# axiom_beta_interface_dummy_v0_13_r1_4.net
KiCad netlist of a schematic drawn in EAGLE
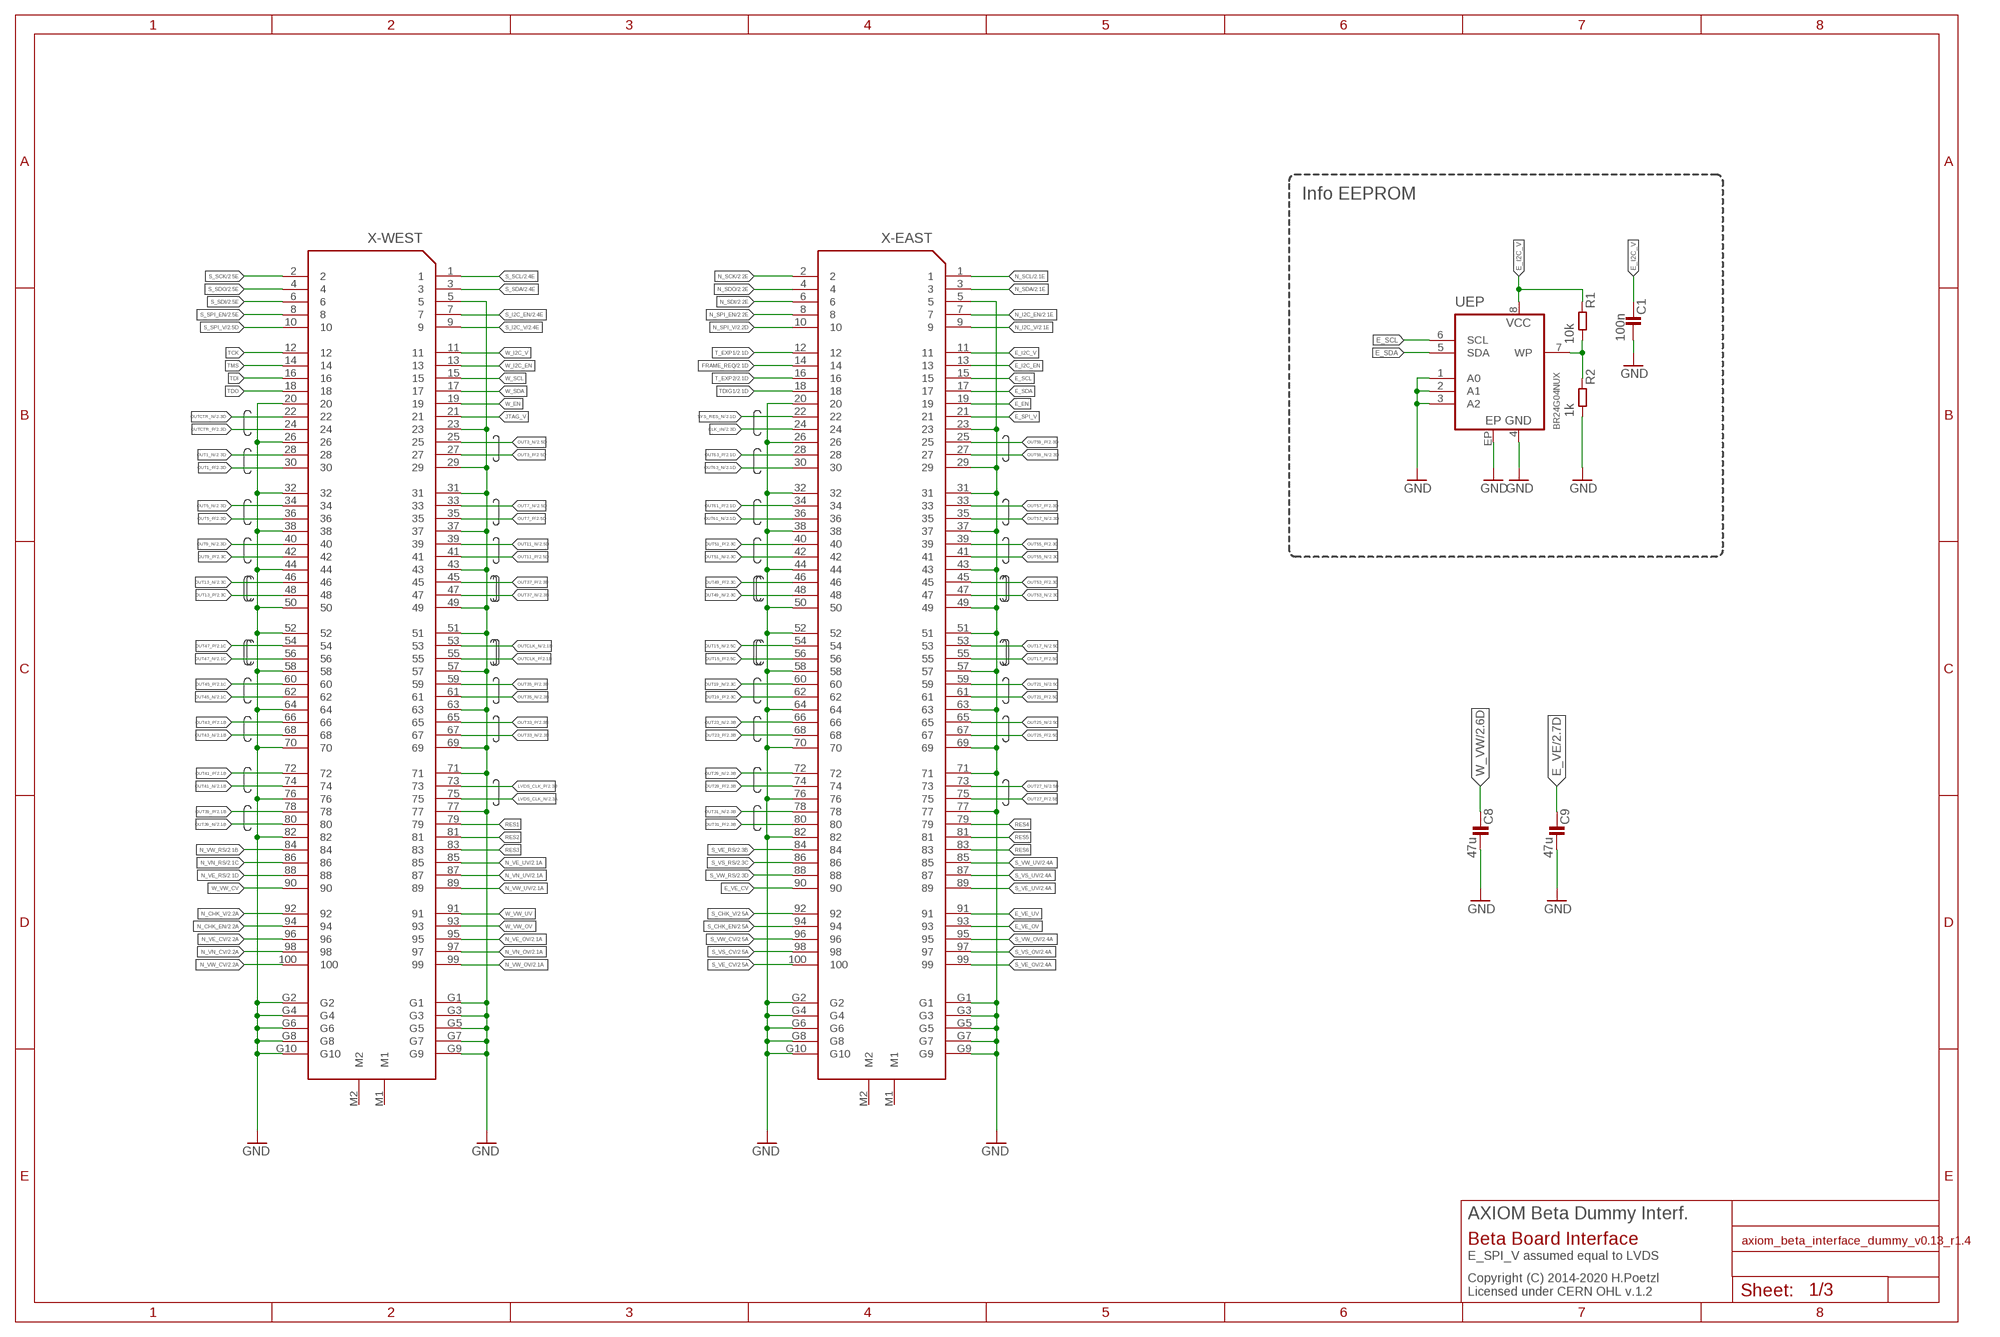
[diagram p0: schematic, sheet 1]
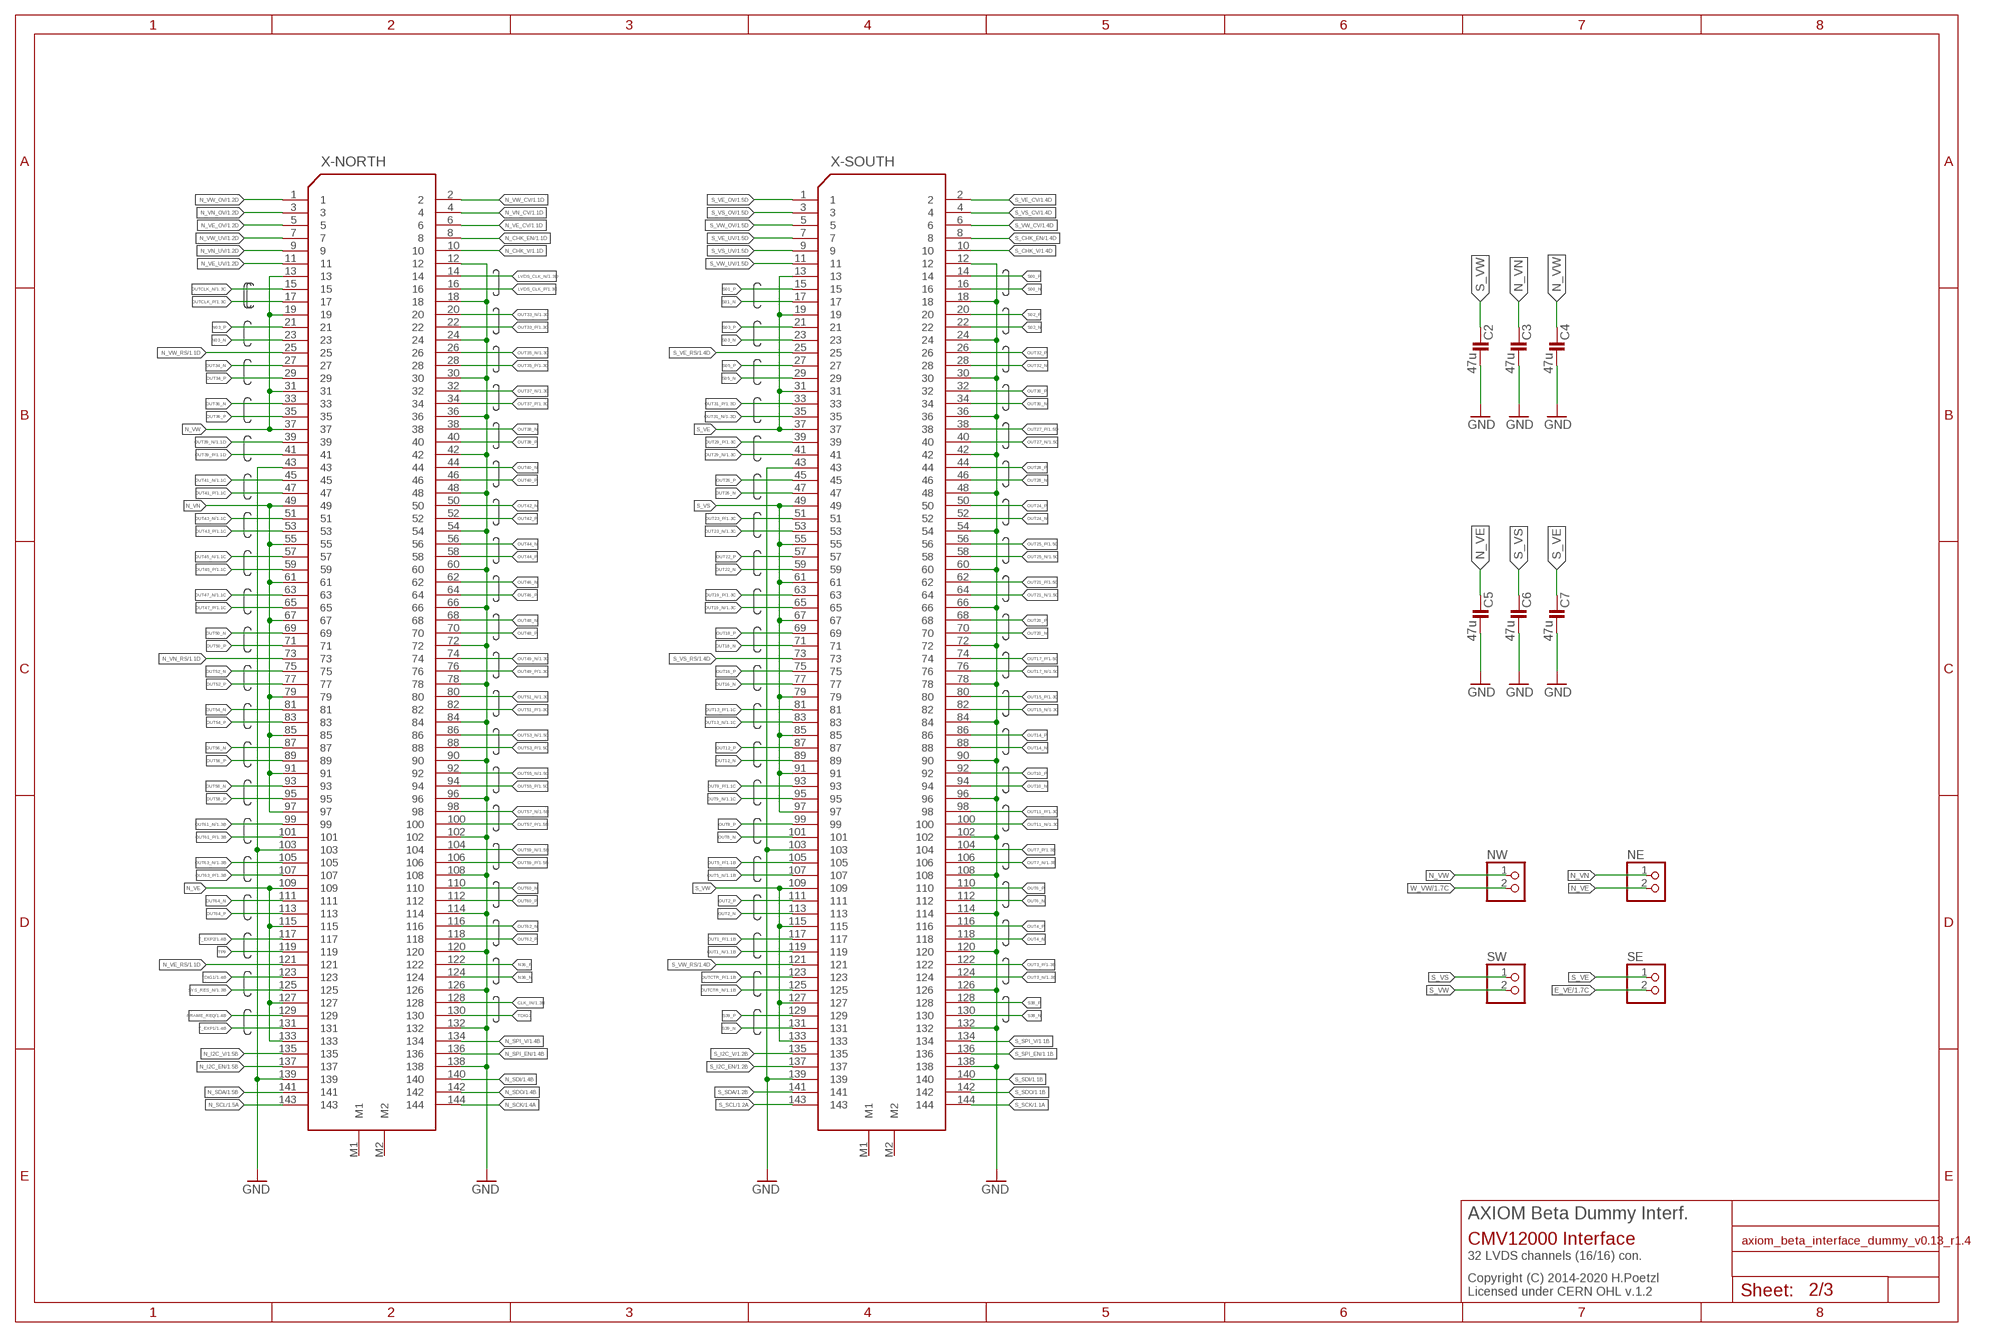
[diagram p1: schematic, sheet 2]
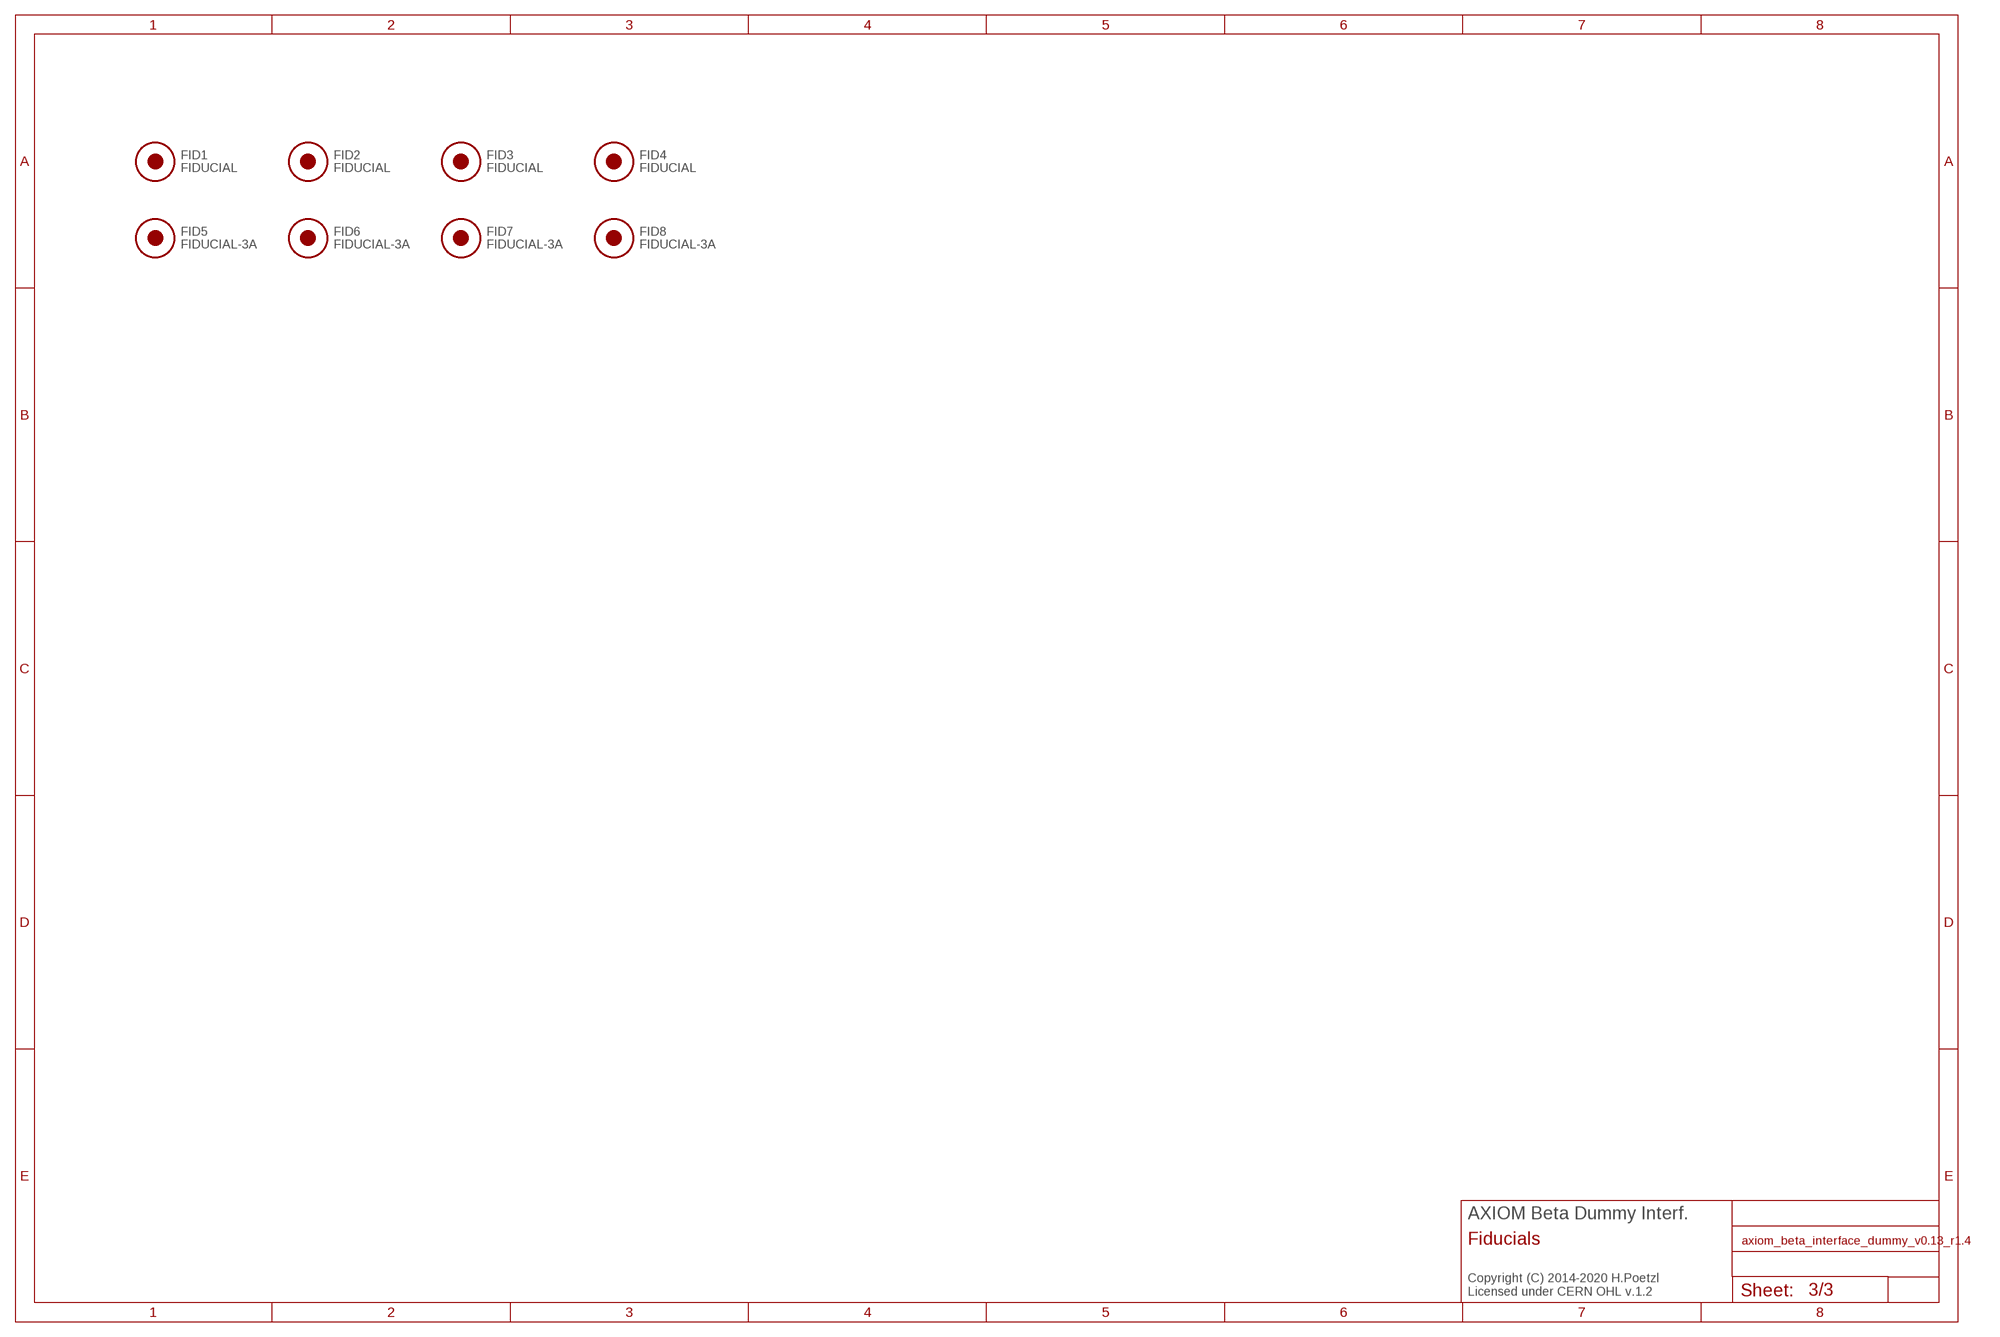
[diagram p2: schematic, sheet 3]

(export (version "E")
  (design (tool "Eeschema 10.0.6"))
  (components
    (comp (ref "C2")
      (value "47u")
      (footprint "eagle-import:0805-B")
      (libsource (lib "eagle-import") (part "C0805-B"))
    )
    (comp (ref "C3")
      (value "47u")
      (footprint "eagle-import:0805-B")
      (libsource (lib "eagle-import") (part "C0805-B"))
    )
    (comp (ref "C4")
      (value "47u")
      (footprint "eagle-import:0805-B")
      (libsource (lib "eagle-import") (part "C0805-B"))
    )
    (comp (ref "C5")
      (value "47u")
      (footprint "eagle-import:0805-B")
      (libsource (lib "eagle-import") (part "C0805-B"))
    )
    (comp (ref "C6")
      (value "47u")
      (footprint "eagle-import:0805-B")
      (libsource (lib "eagle-import") (part "C0805-B"))
    )
    (comp (ref "C7")
      (value "47u")
      (footprint "eagle-import:0805-B")
      (libsource (lib "eagle-import") (part "C0805-B"))
    )
    (comp (ref "NE")
      (value "PINHD-1X02_2.54")
      (footprint "eagle-import:1X02")
      (libsource (lib "eagle-import") (part "PINHD-1X02_2.54"))
    )
    (comp (ref "NW")
      (value "PINHD-1X02_2.54")
      (footprint "eagle-import:1X02")
      (libsource (lib "eagle-import") (part "PINHD-1X02_2.54"))
    )
    (comp (ref "SE")
      (value "PINHD-1X02_2.54")
      (footprint "eagle-import:1X02")
      (libsource (lib "eagle-import") (part "PINHD-1X02_2.54"))
    )
    (comp (ref "SW")
      (value "PINHD-1X02_2.54")
      (footprint "eagle-import:1X02")
      (libsource (lib "eagle-import") (part "PINHD-1X02_2.54"))
    )
    (comp (ref "X-NORTH")
      (value "FX10-144S")
      (footprint "eagle-import:FX10A-144S")
      (libsource (lib "eagle-import") (part "FX10-144S"))
    )
    (comp (ref "X-SOUTH")
      (value "FX10-144S")
      (footprint "eagle-import:FX10A-144S")
      (libsource (lib "eagle-import") (part "FX10-144S"))
    )
    (comp (ref "C1")
      (value "100n")
      (footprint "eagle-import:0402-B")
      (libsource (lib "eagle-import") (part "C0402-B"))
    )
    (comp (ref "C8")
      (value "47u")
      (footprint "eagle-import:0805-B")
      (libsource (lib "eagle-import") (part "C0805-B"))
    )
    (comp (ref "C9")
      (value "47u")
      (footprint "eagle-import:0805-B")
      (libsource (lib "eagle-import") (part "C0805-B"))
    )
    (comp (ref "R1")
      (value "10k")
      (footprint "eagle-import:0402-B")
      (libsource (lib "eagle-import") (part "R0402-B"))
    )
    (comp (ref "R2")
      (value "1k")
      (footprint "eagle-import:0402-B")
      (libsource (lib "eagle-import") (part "R0402-B"))
    )
    (comp (ref "UEP")
      (value "BR24G04NUX")
      (footprint "eagle-import:DFN200X300X100-9N")
      (libsource (lib "eagle-import") (part "BR24G04NUX"))
    )
    (comp (ref "X-EAST")
      (value "FX10-100/10P")
      (footprint "eagle-import:FX10A-100P_10")
      (libsource (lib "eagle-import") (part "FX10-100/10P"))
    )
    (comp (ref "X-WEST")
      (value "FX10-100/10P")
      (footprint "eagle-import:FX10A-100P_10")
      (libsource (lib "eagle-import") (part "FX10-100/10P"))
    )
    (comp (ref "FID1")
      (value "FIDUCIAL")
      (footprint "eagle-import:FID_ARROW")
      (libsource (lib "eagle-import") (part "FIDUCIAL"))
    )
    (comp (ref "FID2")
      (value "FIDUCIAL")
      (footprint "eagle-import:FID_ARROW")
      (libsource (lib "eagle-import") (part "FIDUCIAL"))
    )
    (comp (ref "FID3")
      (value "FIDUCIAL")
      (footprint "eagle-import:FID_ARROW")
      (libsource (lib "eagle-import") (part "FIDUCIAL"))
    )
    (comp (ref "FID4")
      (value "FIDUCIAL")
      (footprint "eagle-import:FID_ARROW")
      (libsource (lib "eagle-import") (part "FIDUCIAL"))
    )
    (comp (ref "FID5")
      (value "FIDUCIAL-3A")
      (footprint "eagle-import:FID_3ARROW")
      (libsource (lib "eagle-import") (part "FIDUCIAL-3A"))
    )
    (comp (ref "FID6")
      (value "FIDUCIAL-3A")
      (footprint "eagle-import:FID_3ARROW")
      (libsource (lib "eagle-import") (part "FIDUCIAL-3A"))
    )
    (comp (ref "FID7")
      (value "FIDUCIAL-3A")
      (footprint "eagle-import:FID_3ARROW")
      (libsource (lib "eagle-import") (part "FIDUCIAL-3A"))
    )
    (comp (ref "FID8")
      (value "FIDUCIAL-3A")
      (footprint "eagle-import:FID_3ARROW")
      (libsource (lib "eagle-import") (part "FIDUCIAL-3A"))
    )
  )
  (nets
    (net (code "1") (name "CLK_IN") (class "Default")
      (node (ref "X-EAST") (pin "24") (pinfunction "24_24") (pintype "bidirectional"))
      (node (ref "X-NORTH") (pin "128") (pinfunction "128_128") (pintype "bidirectional"))
    )
    (net (code "2") (name "E_EN") (class "Default")
      (node (ref "X-EAST") (pin "19") (pinfunction "19_19") (pintype "bidirectional"))
    )
    (net (code "3") (name "E_I2C_EN") (class "Default")
      (node (ref "X-EAST") (pin "13") (pinfunction "13_13") (pintype "bidirectional"))
    )
    (net (code "4") (name "E_I2C_V") (class "Default")
      (node (ref "C1") (pin "1") (pinfunction "1_1") (pintype "passive"))
      (node (ref "R1") (pin "1") (pinfunction "1_1") (pintype "passive"))
      (node (ref "UEP") (pin "8") (pinfunction "VCC_8") (pintype "power_in"))
      (node (ref "X-EAST") (pin "11") (pinfunction "11_11") (pintype "bidirectional"))
    )
    (net (code "5") (name "E_SCL") (class "Default")
      (node (ref "UEP") (pin "6") (pinfunction "SCL_6") (pintype "input"))
      (node (ref "X-EAST") (pin "15") (pinfunction "15_15") (pintype "bidirectional"))
    )
    (net (code "6") (name "E_SDA") (class "Default")
      (node (ref "UEP") (pin "5") (pinfunction "SDA_5") (pintype "bidirectional"))
      (node (ref "X-EAST") (pin "17") (pinfunction "17_17") (pintype "bidirectional"))
    )
    (net (code "7") (name "E_SPI_V") (class "Default")
      (node (ref "X-EAST") (pin "21") (pinfunction "21_21") (pintype "bidirectional"))
    )
    (net (code "8") (name "E_VE") (class "Default")
      (node (ref "C9") (pin "1") (pinfunction "1_1") (pintype "passive"))
      (node (ref "SE") (pin "2") (pinfunction "2_2") (pintype "passive"))
    )
    (net (code "9") (name "E_VE_CV") (class "Default")
      (node (ref "X-EAST") (pin "90") (pinfunction "90_90") (pintype "bidirectional"))
    )
    (net (code "10") (name "E_VE_OV") (class "Default")
      (node (ref "X-EAST") (pin "93") (pinfunction "93_93") (pintype "bidirectional"))
    )
    (net (code "11") (name "E_VE_UV") (class "Default")
      (node (ref "X-EAST") (pin "91") (pinfunction "91_91") (pintype "bidirectional"))
    )
    (net (code "12") (name "FRAME_REQ") (class "Default")
      (node (ref "X-EAST") (pin "14") (pinfunction "14_14") (pintype "bidirectional"))
      (node (ref "X-NORTH") (pin "129") (pinfunction "129_129") (pintype "bidirectional"))
    )
    (net (code "13") (name "GND") (class "Default")
      (node (ref "C1") (pin "2") (pinfunction "2_2") (pintype "passive"))
      (node (ref "C2") (pin "2") (pinfunction "2_2") (pintype "passive"))
      (node (ref "C3") (pin "2") (pinfunction "2_2") (pintype "passive"))
      (node (ref "C4") (pin "2") (pinfunction "2_2") (pintype "passive"))
      (node (ref "C5") (pin "2") (pinfunction "2_2") (pintype "passive"))
      (node (ref "C6") (pin "2") (pinfunction "2_2") (pintype "passive"))
      (node (ref "C7") (pin "2") (pinfunction "2_2") (pintype "passive"))
      (node (ref "C8") (pin "2") (pinfunction "2_2") (pintype "passive"))
      (node (ref "C9") (pin "2") (pinfunction "2_2") (pintype "passive"))
      (node (ref "R2") (pin "2") (pinfunction "2_2") (pintype "passive"))
      (node (ref "UEP") (pin "1") (pinfunction "A0_1") (pintype "input"))
      (node (ref "UEP") (pin "2") (pinfunction "A1_2") (pintype "input"))
      (node (ref "UEP") (pin "3") (pinfunction "A2_3") (pintype "input"))
      (node (ref "UEP") (pin "4") (pinfunction "GND_4") (pintype "passive"))
      (node (ref "UEP") (pin "EP") (pinfunction "EP_EP") (pintype "passive"))
      (node (ref "X-EAST") (pin "20") (pinfunction "20_20") (pintype "bidirectional"))
      (node (ref "X-EAST") (pin "23") (pinfunction "23_23") (pintype "bidirectional"))
      (node (ref "X-EAST") (pin "26") (pinfunction "26_26") (pintype "bidirectional"))
      (node (ref "X-EAST") (pin "29") (pinfunction "29_29") (pintype "bidirectional"))
      (node (ref "X-EAST") (pin "31") (pinfunction "31_31") (pintype "bidirectional"))
      (node (ref "X-EAST") (pin "32") (pinfunction "32_32") (pintype "bidirectional"))
      (node (ref "X-EAST") (pin "37") (pinfunction "37_37") (pintype "bidirectional"))
      (node (ref "X-EAST") (pin "38") (pinfunction "38_38") (pintype "bidirectional"))
      (node (ref "X-EAST") (pin "43") (pinfunction "43_43") (pintype "bidirectional"))
      (node (ref "X-EAST") (pin "44") (pinfunction "44_44") (pintype "bidirectional"))
      (node (ref "X-EAST") (pin "49") (pinfunction "49_49") (pintype "bidirectional"))
      (node (ref "X-EAST") (pin "5") (pinfunction "5_5") (pintype "bidirectional"))
      (node (ref "X-EAST") (pin "50") (pinfunction "50_50") (pintype "bidirectional"))
      (node (ref "X-EAST") (pin "51") (pinfunction "51_51") (pintype "bidirectional"))
      (node (ref "X-EAST") (pin "52") (pinfunction "52_52") (pintype "bidirectional"))
      (node (ref "X-EAST") (pin "57") (pinfunction "57_57") (pintype "bidirectional"))
      (node (ref "X-EAST") (pin "58") (pinfunction "58_58") (pintype "bidirectional"))
      (node (ref "X-EAST") (pin "63") (pinfunction "63_63") (pintype "bidirectional"))
      (node (ref "X-EAST") (pin "64") (pinfunction "64_64") (pintype "bidirectional"))
      (node (ref "X-EAST") (pin "69") (pinfunction "69_69") (pintype "bidirectional"))
      (node (ref "X-EAST") (pin "70") (pinfunction "70_70") (pintype "bidirectional"))
      (node (ref "X-EAST") (pin "71") (pinfunction "71_71") (pintype "bidirectional"))
      (node (ref "X-EAST") (pin "76") (pinfunction "76_76") (pintype "bidirectional"))
      (node (ref "X-EAST") (pin "77") (pinfunction "77_77") (pintype "bidirectional"))
      (node (ref "X-EAST") (pin "82") (pinfunction "82_82") (pintype "bidirectional"))
      (node (ref "X-EAST") (pin "G1") (pinfunction "G1_G1") (pintype "bidirectional"))
      (node (ref "X-EAST") (pin "G10") (pinfunction "G10_G10") (pintype "bidirectional"))
      (node (ref "X-EAST") (pin "G2") (pinfunction "G2_G2") (pintype "bidirectional"))
      (node (ref "X-EAST") (pin "G3") (pinfunction "G3_G3") (pintype "bidirectional"))
      (node (ref "X-EAST") (pin "G4") (pinfunction "G4_G4") (pintype "bidirectional"))
      (node (ref "X-EAST") (pin "G5") (pinfunction "G5_G5") (pintype "bidirectional"))
      (node (ref "X-EAST") (pin "G6") (pinfunction "G6_G6") (pintype "bidirectional"))
      (node (ref "X-EAST") (pin "G7") (pinfunction "G7_G7") (pintype "bidirectional"))
      (node (ref "X-EAST") (pin "G8") (pinfunction "G8_G8") (pintype "bidirectional"))
      (node (ref "X-EAST") (pin "G9") (pinfunction "G9_G9") (pintype "bidirectional"))
      (node (ref "X-NORTH") (pin "102") (pinfunction "102_102") (pintype "bidirectional"))
      (node (ref "X-NORTH") (pin "103") (pinfunction "103_103") (pintype "bidirectional"))
      (node (ref "X-NORTH") (pin "108") (pinfunction "108_108") (pintype "bidirectional"))
      (node (ref "X-NORTH") (pin "114") (pinfunction "114_114") (pintype "bidirectional"))
      (node (ref "X-NORTH") (pin "12") (pinfunction "12_12") (pintype "bidirectional"))
      (node (ref "X-NORTH") (pin "120") (pinfunction "120_120") (pintype "bidirectional"))
      (node (ref "X-NORTH") (pin "126") (pinfunction "126_126") (pintype "bidirectional"))
      (node (ref "X-NORTH") (pin "132") (pinfunction "132_132") (pintype "bidirectional"))
      (node (ref "X-NORTH") (pin "138") (pinfunction "138_138") (pintype "bidirectional"))
      (node (ref "X-NORTH") (pin "139") (pinfunction "139_139") (pintype "bidirectional"))
      (node (ref "X-NORTH") (pin "18") (pinfunction "18_18") (pintype "bidirectional"))
      (node (ref "X-NORTH") (pin "24") (pinfunction "24_24") (pintype "bidirectional"))
      (node (ref "X-NORTH") (pin "30") (pinfunction "30_30") (pintype "bidirectional"))
      (node (ref "X-NORTH") (pin "36") (pinfunction "36_36") (pintype "bidirectional"))
      (node (ref "X-NORTH") (pin "42") (pinfunction "42_42") (pintype "bidirectional"))
      (node (ref "X-NORTH") (pin "43") (pinfunction "43_43") (pintype "bidirectional"))
      (node (ref "X-NORTH") (pin "48") (pinfunction "48_48") (pintype "bidirectional"))
      (node (ref "X-NORTH") (pin "54") (pinfunction "54_54") (pintype "bidirectional"))
      (node (ref "X-NORTH") (pin "60") (pinfunction "60_60") (pintype "bidirectional"))
      (node (ref "X-NORTH") (pin "66") (pinfunction "66_66") (pintype "bidirectional"))
      (node (ref "X-NORTH") (pin "72") (pinfunction "72_72") (pintype "bidirectional"))
      (node (ref "X-NORTH") (pin "78") (pinfunction "78_78") (pintype "bidirectional"))
      (node (ref "X-NORTH") (pin "84") (pinfunction "84_84") (pintype "bidirectional"))
      (node (ref "X-NORTH") (pin "90") (pinfunction "90_90") (pintype "bidirectional"))
      (node (ref "X-NORTH") (pin "96") (pinfunction "96_96") (pintype "bidirectional"))
      (node (ref "X-SOUTH") (pin "102") (pinfunction "102_102") (pintype "bidirectional"))
      (node (ref "X-SOUTH") (pin "103") (pinfunction "103_103") (pintype "bidirectional"))
      (node (ref "X-SOUTH") (pin "108") (pinfunction "108_108") (pintype "bidirectional"))
      (node (ref "X-SOUTH") (pin "114") (pinfunction "114_114") (pintype "bidirectional"))
      (node (ref "X-SOUTH") (pin "12") (pinfunction "12_12") (pintype "bidirectional"))
      (node (ref "X-SOUTH") (pin "120") (pinfunction "120_120") (pintype "bidirectional"))
      (node (ref "X-SOUTH") (pin "126") (pinfunction "126_126") (pintype "bidirectional"))
      (node (ref "X-SOUTH") (pin "132") (pinfunction "132_132") (pintype "bidirectional"))
      (node (ref "X-SOUTH") (pin "138") (pinfunction "138_138") (pintype "bidirectional"))
      (node (ref "X-SOUTH") (pin "139") (pinfunction "139_139") (pintype "bidirectional"))
      (node (ref "X-SOUTH") (pin "18") (pinfunction "18_18") (pintype "bidirectional"))
      (node (ref "X-SOUTH") (pin "24") (pinfunction "24_24") (pintype "bidirectional"))
      (node (ref "X-SOUTH") (pin "30") (pinfunction "30_30") (pintype "bidirectional"))
      (node (ref "X-SOUTH") (pin "36") (pinfunction "36_36") (pintype "bidirectional"))
      (node (ref "X-SOUTH") (pin "42") (pinfunction "42_42") (pintype "bidirectional"))
      (node (ref "X-SOUTH") (pin "43") (pinfunction "43_43") (pintype "bidirectional"))
      (node (ref "X-SOUTH") (pin "48") (pinfunction "48_48") (pintype "bidirectional"))
      (node (ref "X-SOUTH") (pin "54") (pinfunction "54_54") (pintype "bidirectional"))
      (node (ref "X-SOUTH") (pin "60") (pinfunction "60_60") (pintype "bidirectional"))
      (node (ref "X-SOUTH") (pin "66") (pinfunction "66_66") (pintype "bidirectional"))
      (node (ref "X-SOUTH") (pin "72") (pinfunction "72_72") (pintype "bidirectional"))
      (node (ref "X-SOUTH") (pin "78") (pinfunction "78_78") (pintype "bidirectional"))
      (node (ref "X-SOUTH") (pin "84") (pinfunction "84_84") (pintype "bidirectional"))
      (node (ref "X-SOUTH") (pin "90") (pinfunction "90_90") (pintype "bidirectional"))
      (node (ref "X-SOUTH") (pin "96") (pinfunction "96_96") (pintype "bidirectional"))
      (node (ref "X-WEST") (pin "20") (pinfunction "20_20") (pintype "bidirectional"))
      (node (ref "X-WEST") (pin "23") (pinfunction "23_23") (pintype "bidirectional"))
      (node (ref "X-WEST") (pin "26") (pinfunction "26_26") (pintype "bidirectional"))
      (node (ref "X-WEST") (pin "29") (pinfunction "29_29") (pintype "bidirectional"))
      (node (ref "X-WEST") (pin "31") (pinfunction "31_31") (pintype "bidirectional"))
      (node (ref "X-WEST") (pin "32") (pinfunction "32_32") (pintype "bidirectional"))
      (node (ref "X-WEST") (pin "37") (pinfunction "37_37") (pintype "bidirectional"))
      (node (ref "X-WEST") (pin "38") (pinfunction "38_38") (pintype "bidirectional"))
      (node (ref "X-WEST") (pin "43") (pinfunction "43_43") (pintype "bidirectional"))
      (node (ref "X-WEST") (pin "44") (pinfunction "44_44") (pintype "bidirectional"))
      (node (ref "X-WEST") (pin "49") (pinfunction "49_49") (pintype "bidirectional"))
      (node (ref "X-WEST") (pin "5") (pinfunction "5_5") (pintype "bidirectional"))
      (node (ref "X-WEST") (pin "50") (pinfunction "50_50") (pintype "bidirectional"))
      (node (ref "X-WEST") (pin "51") (pinfunction "51_51") (pintype "bidirectional"))
      (node (ref "X-WEST") (pin "52") (pinfunction "52_52") (pintype "bidirectional"))
      (node (ref "X-WEST") (pin "57") (pinfunction "57_57") (pintype "bidirectional"))
      (node (ref "X-WEST") (pin "58") (pinfunction "58_58") (pintype "bidirectional"))
      (node (ref "X-WEST") (pin "63") (pinfunction "63_63") (pintype "bidirectional"))
      (node (ref "X-WEST") (pin "64") (pinfunction "64_64") (pintype "bidirectional"))
      (node (ref "X-WEST") (pin "69") (pinfunction "69_69") (pintype "bidirectional"))
      (node (ref "X-WEST") (pin "70") (pinfunction "70_70") (pintype "bidirectional"))
      (node (ref "X-WEST") (pin "71") (pinfunction "71_71") (pintype "bidirectional"))
      (node (ref "X-WEST") (pin "76") (pinfunction "76_76") (pintype "bidirectional"))
      (node (ref "X-WEST") (pin "77") (pinfunction "77_77") (pintype "bidirectional"))
      (node (ref "X-WEST") (pin "82") (pinfunction "82_82") (pintype "bidirectional"))
      (node (ref "X-WEST") (pin "G1") (pinfunction "G1_G1") (pintype "bidirectional"))
      (node (ref "X-WEST") (pin "G10") (pinfunction "G10_G10") (pintype "bidirectional"))
      (node (ref "X-WEST") (pin "G2") (pinfunction "G2_G2") (pintype "bidirectional"))
      (node (ref "X-WEST") (pin "G3") (pinfunction "G3_G3") (pintype "bidirectional"))
      (node (ref "X-WEST") (pin "G4") (pinfunction "G4_G4") (pintype "bidirectional"))
      (node (ref "X-WEST") (pin "G5") (pinfunction "G5_G5") (pintype "bidirectional"))
      (node (ref "X-WEST") (pin "G6") (pinfunction "G6_G6") (pintype "bidirectional"))
      (node (ref "X-WEST") (pin "G7") (pinfunction "G7_G7") (pintype "bidirectional"))
      (node (ref "X-WEST") (pin "G8") (pinfunction "G8_G8") (pintype "bidirectional"))
      (node (ref "X-WEST") (pin "G9") (pinfunction "G9_G9") (pintype "bidirectional"))
    )
    (net (code "14") (name "JTAG_V") (class "Default")
      (node (ref "X-WEST") (pin "21") (pinfunction "21_21") (pintype "bidirectional"))
    )
    (net (code "15") (name "LVDS_CLK_N") (class "Default")
      (node (ref "X-NORTH") (pin "14") (pinfunction "14_14") (pintype "bidirectional"))
      (node (ref "X-WEST") (pin "75") (pinfunction "75_75") (pintype "bidirectional"))
    )
    (net (code "16") (name "LVDS_CLK_P") (class "Default")
      (node (ref "X-NORTH") (pin "16") (pinfunction "16_16") (pintype "bidirectional"))
      (node (ref "X-WEST") (pin "73") (pinfunction "73_73") (pintype "bidirectional"))
    )
    (net (code "17") (name "N03_N") (class "Default")
      (node (ref "X-NORTH") (pin "23") (pinfunction "23_23") (pintype "bidirectional"))
    )
    (net (code "18") (name "N03_P") (class "Default")
      (node (ref "X-NORTH") (pin "21") (pinfunction "21_21") (pintype "bidirectional"))
    )
    (net (code "19") (name "N36_N") (class "Default")
      (node (ref "X-NORTH") (pin "124") (pinfunction "124_124") (pintype "bidirectional"))
    )
    (net (code "20") (name "N36_P") (class "Default")
      (node (ref "X-NORTH") (pin "122") (pinfunction "122_122") (pintype "bidirectional"))
    )
    (net (code "21") (name "N_CHK_EN") (class "Default")
      (node (ref "X-NORTH") (pin "8") (pinfunction "8_8") (pintype "bidirectional"))
      (node (ref "X-WEST") (pin "94") (pinfunction "94_94") (pintype "bidirectional"))
    )
    (net (code "22") (name "N_CHK_V") (class "Default")
      (node (ref "X-NORTH") (pin "10") (pinfunction "10_10") (pintype "bidirectional"))
      (node (ref "X-WEST") (pin "92") (pinfunction "92_92") (pintype "bidirectional"))
    )
    (net (code "23") (name "N_I2C_EN") (class "Default")
      (node (ref "X-EAST") (pin "7") (pinfunction "7_7") (pintype "bidirectional"))
      (node (ref "X-NORTH") (pin "137") (pinfunction "137_137") (pintype "bidirectional"))
    )
    (net (code "24") (name "N_I2C_V") (class "Default")
      (node (ref "X-EAST") (pin "9") (pinfunction "9_9") (pintype "bidirectional"))
      (node (ref "X-NORTH") (pin "135") (pinfunction "135_135") (pintype "bidirectional"))
    )
    (net (code "25") (name "N_SCK") (class "Default")
      (node (ref "X-EAST") (pin "2") (pinfunction "2_2") (pintype "bidirectional"))
      (node (ref "X-NORTH") (pin "144") (pinfunction "144_144") (pintype "bidirectional"))
    )
    (net (code "26") (name "N_SCL") (class "Default")
      (node (ref "X-EAST") (pin "1") (pinfunction "1_1") (pintype "bidirectional"))
      (node (ref "X-NORTH") (pin "143") (pinfunction "143_143") (pintype "bidirectional"))
    )
    (net (code "27") (name "N_SDA") (class "Default")
      (node (ref "X-EAST") (pin "3") (pinfunction "3_3") (pintype "bidirectional"))
      (node (ref "X-NORTH") (pin "141") (pinfunction "141_141") (pintype "bidirectional"))
    )
    (net (code "28") (name "N_SDI") (class "Default")
      (node (ref "X-EAST") (pin "6") (pinfunction "6_6") (pintype "bidirectional"))
      (node (ref "X-NORTH") (pin "140") (pinfunction "140_140") (pintype "bidirectional"))
    )
    (net (code "29") (name "N_SDO") (class "Default")
      (node (ref "X-EAST") (pin "4") (pinfunction "4_4") (pintype "bidirectional"))
      (node (ref "X-NORTH") (pin "142") (pinfunction "142_142") (pintype "bidirectional"))
    )
    (net (code "30") (name "N_SPI_EN") (class "Default")
      (node (ref "X-EAST") (pin "8") (pinfunction "8_8") (pintype "bidirectional"))
      (node (ref "X-NORTH") (pin "136") (pinfunction "136_136") (pintype "bidirectional"))
    )
    (net (code "31") (name "N_SPI_V") (class "Default")
      (node (ref "X-EAST") (pin "10") (pinfunction "10_10") (pintype "bidirectional"))
      (node (ref "X-NORTH") (pin "134") (pinfunction "134_134") (pintype "bidirectional"))
    )
    (net (code "32") (name "N_VE") (class "Default")
      (node (ref "C5") (pin "1") (pinfunction "1_1") (pintype "passive"))
      (node (ref "NE") (pin "2") (pinfunction "2_2") (pintype "passive"))
      (node (ref "X-NORTH") (pin "109") (pinfunction "109_109") (pintype "bidirectional"))
      (node (ref "X-NORTH") (pin "115") (pinfunction "115_115") (pintype "bidirectional"))
      (node (ref "X-NORTH") (pin "127") (pinfunction "127_127") (pintype "bidirectional"))
      (node (ref "X-NORTH") (pin "133") (pinfunction "133_133") (pintype "bidirectional"))
    )
    (net (code "33") (name "N_VE_CV") (class "Default")
      (node (ref "X-NORTH") (pin "6") (pinfunction "6_6") (pintype "bidirectional"))
      (node (ref "X-WEST") (pin "96") (pinfunction "96_96") (pintype "bidirectional"))
    )
    (net (code "34") (name "N_VE_OV") (class "Default")
      (node (ref "X-NORTH") (pin "5") (pinfunction "5_5") (pintype "bidirectional"))
      (node (ref "X-WEST") (pin "95") (pinfunction "95_95") (pintype "bidirectional"))
    )
    (net (code "35") (name "N_VE_RS") (class "Default")
      (node (ref "X-NORTH") (pin "121") (pinfunction "121_121") (pintype "bidirectional"))
      (node (ref "X-WEST") (pin "88") (pinfunction "88_88") (pintype "bidirectional"))
    )
    (net (code "36") (name "N_VE_UV") (class "Default")
      (node (ref "X-NORTH") (pin "11") (pinfunction "11_11") (pintype "bidirectional"))
      (node (ref "X-WEST") (pin "85") (pinfunction "85_85") (pintype "bidirectional"))
    )
    (net (code "37") (name "N_VN") (class "Default")
      (node (ref "C3") (pin "1") (pinfunction "1_1") (pintype "passive"))
      (node (ref "NE") (pin "1") (pinfunction "1_1") (pintype "passive"))
      (node (ref "X-NORTH") (pin "49") (pinfunction "49_49") (pintype "bidirectional"))
      (node (ref "X-NORTH") (pin "55") (pinfunction "55_55") (pintype "bidirectional"))
      (node (ref "X-NORTH") (pin "61") (pinfunction "61_61") (pintype "bidirectional"))
      (node (ref "X-NORTH") (pin "67") (pinfunction "67_67") (pintype "bidirectional"))
      (node (ref "X-NORTH") (pin "79") (pinfunction "79_79") (pintype "bidirectional"))
      (node (ref "X-NORTH") (pin "85") (pinfunction "85_85") (pintype "bidirectional"))
      (node (ref "X-NORTH") (pin "91") (pinfunction "91_91") (pintype "bidirectional"))
      (node (ref "X-NORTH") (pin "97") (pinfunction "97_97") (pintype "bidirectional"))
    )
    (net (code "38") (name "N_VN_CV") (class "Default")
      (node (ref "X-NORTH") (pin "4") (pinfunction "4_4") (pintype "bidirectional"))
      (node (ref "X-WEST") (pin "98") (pinfunction "98_98") (pintype "bidirectional"))
    )
    (net (code "39") (name "N_VN_OV") (class "Default")
      (node (ref "X-NORTH") (pin "3") (pinfunction "3_3") (pintype "bidirectional"))
      (node (ref "X-WEST") (pin "97") (pinfunction "97_97") (pintype "bidirectional"))
    )
    (net (code "40") (name "N_VN_RS") (class "Default")
      (node (ref "X-NORTH") (pin "73") (pinfunction "73_73") (pintype "bidirectional"))
      (node (ref "X-WEST") (pin "86") (pinfunction "86_86") (pintype "bidirectional"))
    )
    (net (code "41") (name "N_VN_UV") (class "Default")
      (node (ref "X-NORTH") (pin "9") (pinfunction "9_9") (pintype "bidirectional"))
      (node (ref "X-WEST") (pin "87") (pinfunction "87_87") (pintype "bidirectional"))
    )
    (net (code "42") (name "N_VW") (class "Default")
      (node (ref "C4") (pin "1") (pinfunction "1_1") (pintype "passive"))
      (node (ref "NW") (pin "1") (pinfunction "1_1") (pintype "passive"))
      (node (ref "X-NORTH") (pin "13") (pinfunction "13_13") (pintype "bidirectional"))
      (node (ref "X-NORTH") (pin "19") (pinfunction "19_19") (pintype "bidirectional"))
      (node (ref "X-NORTH") (pin "31") (pinfunction "31_31") (pintype "bidirectional"))
      (node (ref "X-NORTH") (pin "37") (pinfunction "37_37") (pintype "bidirectional"))
    )
    (net (code "43") (name "N_VW_CV") (class "Default")
      (node (ref "X-NORTH") (pin "2") (pinfunction "2_2") (pintype "bidirectional"))
      (node (ref "X-WEST") (pin "100") (pinfunction "100_100") (pintype "bidirectional"))
    )
    (net (code "44") (name "N_VW_OV") (class "Default")
      (node (ref "X-NORTH") (pin "1") (pinfunction "1_1") (pintype "bidirectional"))
      (node (ref "X-WEST") (pin "99") (pinfunction "99_99") (pintype "bidirectional"))
    )
    (net (code "45") (name "N_VW_RS") (class "Default")
      (node (ref "X-NORTH") (pin "25") (pinfunction "25_25") (pintype "bidirectional"))
      (node (ref "X-WEST") (pin "84") (pinfunction "84_84") (pintype "bidirectional"))
    )
    (net (code "46") (name "N_VW_UV") (class "Default")
      (node (ref "X-NORTH") (pin "7") (pinfunction "7_7") (pintype "bidirectional"))
      (node (ref "X-WEST") (pin "89") (pinfunction "89_89") (pintype "bidirectional"))
    )
    (net (code "47") (name "Net-(UEP-WP)") (class "Default")
      (node (ref "R1") (pin "2") (pinfunction "2_2") (pintype "passive"))
      (node (ref "R2") (pin "1") (pinfunction "1_1") (pintype "passive"))
      (node (ref "UEP") (pin "7") (pinfunction "WP_7") (pintype "input"))
    )
    (net (code "48") (name "OUT1_N") (class "Default")
      (node (ref "X-SOUTH") (pin "119") (pinfunction "119_119") (pintype "bidirectional"))
      (node (ref "X-WEST") (pin "28") (pinfunction "28_28") (pintype "bidirectional"))
    )
    (net (code "49") (name "OUT1_P") (class "Default")
      (node (ref "X-SOUTH") (pin "117") (pinfunction "117_117") (pintype "bidirectional"))
      (node (ref "X-WEST") (pin "30") (pinfunction "30_30") (pintype "bidirectional"))
    )
    (net (code "50") (name "OUT2_N") (class "Default")
      (node (ref "X-SOUTH") (pin "113") (pinfunction "113_113") (pintype "bidirectional"))
    )
    (net (code "51") (name "OUT2_P") (class "Default")
      (node (ref "X-SOUTH") (pin "111") (pinfunction "111_111") (pintype "bidirectional"))
    )
    (net (code "52") (name "OUT3_N") (class "Default")
      (node (ref "X-SOUTH") (pin "124") (pinfunction "124_124") (pintype "bidirectional"))
      (node (ref "X-WEST") (pin "25") (pinfunction "25_25") (pintype "bidirectional"))
    )
    (net (code "53") (name "OUT3_P") (class "Default")
      (node (ref "X-SOUTH") (pin "122") (pinfunction "122_122") (pintype "bidirectional"))
      (node (ref "X-WEST") (pin "27") (pinfunction "27_27") (pintype "bidirectional"))
    )
    (net (code "54") (name "OUT4_N") (class "Default")
      (node (ref "X-SOUTH") (pin "118") (pinfunction "118_118") (pintype "bidirectional"))
    )
    (net (code "55") (name "OUT4_P") (class "Default")
      (node (ref "X-SOUTH") (pin "116") (pinfunction "116_116") (pintype "bidirectional"))
    )
    (net (code "56") (name "OUT5_N") (class "Default")
      (node (ref "X-SOUTH") (pin "107") (pinfunction "107_107") (pintype "bidirectional"))
      (node (ref "X-WEST") (pin "34") (pinfunction "34_34") (pintype "bidirectional"))
    )
    (net (code "57") (name "OUT5_P") (class "Default")
      (node (ref "X-SOUTH") (pin "105") (pinfunction "105_105") (pintype "bidirectional"))
      (node (ref "X-WEST") (pin "36") (pinfunction "36_36") (pintype "bidirectional"))
    )
    (net (code "58") (name "OUT6_N") (class "Default")
      (node (ref "X-SOUTH") (pin "112") (pinfunction "112_112") (pintype "bidirectional"))
    )
    (net (code "59") (name "OUT6_P") (class "Default")
      (node (ref "X-SOUTH") (pin "110") (pinfunction "110_110") (pintype "bidirectional"))
    )
    (net (code "60") (name "OUT7_N") (class "Default")
      (node (ref "X-SOUTH") (pin "106") (pinfunction "106_106") (pintype "bidirectional"))
      (node (ref "X-WEST") (pin "33") (pinfunction "33_33") (pintype "bidirectional"))
    )
    (net (code "61") (name "OUT7_P") (class "Default")
      (node (ref "X-SOUTH") (pin "104") (pinfunction "104_104") (pintype "bidirectional"))
      (node (ref "X-WEST") (pin "35") (pinfunction "35_35") (pintype "bidirectional"))
    )
    (net (code "62") (name "OUT8_N") (class "Default")
      (node (ref "X-SOUTH") (pin "101") (pinfunction "101_101") (pintype "bidirectional"))
    )
    (net (code "63") (name "OUT8_P") (class "Default")
      (node (ref "X-SOUTH") (pin "99") (pinfunction "99_99") (pintype "bidirectional"))
    )
    (net (code "64") (name "OUT9_N") (class "Default")
      (node (ref "X-SOUTH") (pin "95") (pinfunction "95_95") (pintype "bidirectional"))
      (node (ref "X-WEST") (pin "40") (pinfunction "40_40") (pintype "bidirectional"))
    )
    (net (code "65") (name "OUT9_P") (class "Default")
      (node (ref "X-SOUTH") (pin "93") (pinfunction "93_93") (pintype "bidirectional"))
      (node (ref "X-WEST") (pin "42") (pinfunction "42_42") (pintype "bidirectional"))
    )
    (net (code "66") (name "OUT10_N") (class "Default")
      (node (ref "X-SOUTH") (pin "94") (pinfunction "94_94") (pintype "bidirectional"))
    )
    (net (code "67") (name "OUT10_P") (class "Default")
      (node (ref "X-SOUTH") (pin "92") (pinfunction "92_92") (pintype "bidirectional"))
    )
    (net (code "68") (name "OUT11_N") (class "Default")
      (node (ref "X-SOUTH") (pin "100") (pinfunction "100_100") (pintype "bidirectional"))
      (node (ref "X-WEST") (pin "39") (pinfunction "39_39") (pintype "bidirectional"))
    )
    (net (code "69") (name "OUT11_P") (class "Default")
      (node (ref "X-SOUTH") (pin "98") (pinfunction "98_98") (pintype "bidirectional"))
      (node (ref "X-WEST") (pin "41") (pinfunction "41_41") (pintype "bidirectional"))
    )
    (net (code "70") (name "OUT12_N") (class "Default")
      (node (ref "X-SOUTH") (pin "89") (pinfunction "89_89") (pintype "bidirectional"))
    )
    (net (code "71") (name "OUT12_P") (class "Default")
      (node (ref "X-SOUTH") (pin "87") (pinfunction "87_87") (pintype "bidirectional"))
    )
    (net (code "72") (name "OUT13_N") (class "Default")
      (node (ref "X-SOUTH") (pin "83") (pinfunction "83_83") (pintype "bidirectional"))
      (node (ref "X-WEST") (pin "46") (pinfunction "46_46") (pintype "bidirectional"))
    )
    (net (code "73") (name "OUT13_P") (class "Default")
      (node (ref "X-SOUTH") (pin "81") (pinfunction "81_81") (pintype "bidirectional"))
      (node (ref "X-WEST") (pin "48") (pinfunction "48_48") (pintype "bidirectional"))
    )
    (net (code "74") (name "OUT14_N") (class "Default")
      (node (ref "X-SOUTH") (pin "88") (pinfunction "88_88") (pintype "bidirectional"))
    )
    (net (code "75") (name "OUT14_P") (class "Default")
      (node (ref "X-SOUTH") (pin "86") (pinfunction "86_86") (pintype "bidirectional"))
    )
    (net (code "76") (name "OUT15_N") (class "Default")
      (node (ref "X-EAST") (pin "54") (pinfunction "54_54") (pintype "bidirectional"))
      (node (ref "X-SOUTH") (pin "82") (pinfunction "82_82") (pintype "bidirectional"))
    )
    (net (code "77") (name "OUT15_P") (class "Default")
      (node (ref "X-EAST") (pin "56") (pinfunction "56_56") (pintype "bidirectional"))
      (node (ref "X-SOUTH") (pin "80") (pinfunction "80_80") (pintype "bidirectional"))
    )
    (net (code "78") (name "OUT16_N") (class "Default")
      (node (ref "X-SOUTH") (pin "77") (pinfunction "77_77") (pintype "bidirectional"))
    )
    (net (code "79") (name "OUT16_P") (class "Default")
      (node (ref "X-SOUTH") (pin "75") (pinfunction "75_75") (pintype "bidirectional"))
    )
    (net (code "80") (name "OUT17_N") (class "Default")
      (node (ref "X-EAST") (pin "53") (pinfunction "53_53") (pintype "bidirectional"))
      (node (ref "X-SOUTH") (pin "76") (pinfunction "76_76") (pintype "bidirectional"))
    )
    (net (code "81") (name "OUT17_P") (class "Default")
      (node (ref "X-EAST") (pin "55") (pinfunction "55_55") (pintype "bidirectional"))
      (node (ref "X-SOUTH") (pin "74") (pinfunction "74_74") (pintype "bidirectional"))
    )
    (net (code "82") (name "OUT18_N") (class "Default")
      (node (ref "X-SOUTH") (pin "71") (pinfunction "71_71") (pintype "bidirectional"))
    )
    (net (code "83") (name "OUT18_P") (class "Default")
      (node (ref "X-SOUTH") (pin "69") (pinfunction "69_69") (pintype "bidirectional"))
    )
    (net (code "84") (name "OUT19_N") (class "Default")
      (node (ref "X-EAST") (pin "60") (pinfunction "60_60") (pintype "bidirectional"))
      (node (ref "X-SOUTH") (pin "65") (pinfunction "65_65") (pintype "bidirectional"))
    )
    (net (code "85") (name "OUT19_P") (class "Default")
      (node (ref "X-EAST") (pin "62") (pinfunction "62_62") (pintype "bidirectional"))
      (node (ref "X-SOUTH") (pin "63") (pinfunction "63_63") (pintype "bidirectional"))
    )
    (net (code "86") (name "OUT20_N") (class "Default")
      (node (ref "X-SOUTH") (pin "70") (pinfunction "70_70") (pintype "bidirectional"))
    )
    (net (code "87") (name "OUT20_P") (class "Default")
      (node (ref "X-SOUTH") (pin "68") (pinfunction "68_68") (pintype "bidirectional"))
    )
    (net (code "88") (name "OUT21_N") (class "Default")
      (node (ref "X-EAST") (pin "59") (pinfunction "59_59") (pintype "bidirectional"))
      (node (ref "X-SOUTH") (pin "64") (pinfunction "64_64") (pintype "bidirectional"))
    )
    (net (code "89") (name "OUT21_P") (class "Default")
      (node (ref "X-EAST") (pin "61") (pinfunction "61_61") (pintype "bidirectional"))
      (node (ref "X-SOUTH") (pin "62") (pinfunction "62_62") (pintype "bidirectional"))
    )
    (net (code "90") (name "OUT22_N") (class "Default")
      (node (ref "X-SOUTH") (pin "59") (pinfunction "59_59") (pintype "bidirectional"))
    )
    (net (code "91") (name "OUT22_P") (class "Default")
      (node (ref "X-SOUTH") (pin "57") (pinfunction "57_57") (pintype "bidirectional"))
    )
    (net (code "92") (name "OUT23_N") (class "Default")
      (node (ref "X-EAST") (pin "66") (pinfunction "66_66") (pintype "bidirectional"))
      (node (ref "X-SOUTH") (pin "53") (pinfunction "53_53") (pintype "bidirectional"))
    )
    (net (code "93") (name "OUT23_P") (class "Default")
      (node (ref "X-EAST") (pin "68") (pinfunction "68_68") (pintype "bidirectional"))
      (node (ref "X-SOUTH") (pin "51") (pinfunction "51_51") (pintype "bidirectional"))
    )
    (net (code "94") (name "OUT24_N") (class "Default")
      (node (ref "X-SOUTH") (pin "52") (pinfunction "52_52") (pintype "bidirectional"))
    )
    (net (code "95") (name "OUT24_P") (class "Default")
      (node (ref "X-SOUTH") (pin "50") (pinfunction "50_50") (pintype "bidirectional"))
    )
    (net (code "96") (name "OUT25_N") (class "Default")
      (node (ref "X-EAST") (pin "65") (pinfunction "65_65") (pintype "bidirectional"))
      (node (ref "X-SOUTH") (pin "58") (pinfunction "58_58") (pintype "bidirectional"))
    )
    (net (code "97") (name "OUT25_P") (class "Default")
      (node (ref "X-EAST") (pin "67") (pinfunction "67_67") (pintype "bidirectional"))
      (node (ref "X-SOUTH") (pin "56") (pinfunction "56_56") (pintype "bidirectional"))
    )
    (net (code "98") (name "OUT26_N") (class "Default")
      (node (ref "X-SOUTH") (pin "47") (pinfunction "47_47") (pintype "bidirectional"))
    )
    (net (code "99") (name "OUT26_P") (class "Default")
      (node (ref "X-SOUTH") (pin "45") (pinfunction "45_45") (pintype "bidirectional"))
    )
    (net (code "100") (name "OUT27_N") (class "Default")
      (node (ref "X-EAST") (pin "73") (pinfunction "73_73") (pintype "bidirectional"))
      (node (ref "X-SOUTH") (pin "40") (pinfunction "40_40") (pintype "bidirectional"))
    )
    (net (code "101") (name "OUT27_P") (class "Default")
      (node (ref "X-EAST") (pin "75") (pinfunction "75_75") (pintype "bidirectional"))
      (node (ref "X-SOUTH") (pin "38") (pinfunction "38_38") (pintype "bidirectional"))
    )
    (net (code "102") (name "OUT28_N") (class "Default")
      (node (ref "X-SOUTH") (pin "46") (pinfunction "46_46") (pintype "bidirectional"))
    )
    (net (code "103") (name "OUT28_P") (class "Default")
      (node (ref "X-SOUTH") (pin "44") (pinfunction "44_44") (pintype "bidirectional"))
    )
    (net (code "104") (name "OUT29_N") (class "Default")
      (node (ref "X-EAST") (pin "72") (pinfunction "72_72") (pintype "bidirectional"))
      (node (ref "X-SOUTH") (pin "41") (pinfunction "41_41") (pintype "bidirectional"))
    )
    (net (code "105") (name "OUT29_P") (class "Default")
      (node (ref "X-EAST") (pin "74") (pinfunction "74_74") (pintype "bidirectional"))
      (node (ref "X-SOUTH") (pin "39") (pinfunction "39_39") (pintype "bidirectional"))
    )
    (net (code "106") (name "OUT30_N") (class "Default")
      (node (ref "X-SOUTH") (pin "34") (pinfunction "34_34") (pintype "bidirectional"))
    )
    (net (code "107") (name "OUT30_P") (class "Default")
      (node (ref "X-SOUTH") (pin "32") (pinfunction "32_32") (pintype "bidirectional"))
    )
    (net (code "108") (name "OUT31_N") (class "Default")
      (node (ref "X-EAST") (pin "78") (pinfunction "78_78") (pintype "bidirectional"))
      (node (ref "X-SOUTH") (pin "35") (pinfunction "35_35") (pintype "bidirectional"))
    )
    (net (code "109") (name "OUT31_P") (class "Default")
      (node (ref "X-EAST") (pin "80") (pinfunction "80_80") (pintype "bidirectional"))
      (node (ref "X-SOUTH") (pin "33") (pinfunction "33_33") (pintype "bidirectional"))
    )
    (net (code "110") (name "OUT32_N") (class "Default")
      (node (ref "X-SOUTH") (pin "28") (pinfunction "28_28") (pintype "bidirectional"))
    )
    (net (code "111") (name "OUT32_P") (class "Default")
      (node (ref "X-SOUTH") (pin "26") (pinfunction "26_26") (pintype "bidirectional"))
    )
    (net (code "112") (name "OUT33_N") (class "Default")
      (node (ref "X-NORTH") (pin "20") (pinfunction "20_20") (pintype "bidirectional"))
      (node (ref "X-WEST") (pin "67") (pinfunction "67_67") (pintype "bidirectional"))
    )
    (net (code "113") (name "OUT33_P") (class "Default")
      (node (ref "X-NORTH") (pin "22") (pinfunction "22_22") (pintype "bidirectional"))
      (node (ref "X-WEST") (pin "65") (pinfunction "65_65") (pintype "bidirectional"))
    )
    (net (code "114") (name "OUT34_N") (class "Default")
      (node (ref "X-NORTH") (pin "27") (pinfunction "27_27") (pintype "bidirectional"))
    )
    (net (code "115") (name "OUT34_P") (class "Default")
      (node (ref "X-NORTH") (pin "29") (pinfunction "29_29") (pintype "bidirectional"))
    )
    (net (code "116") (name "OUT35_N") (class "Default")
      (node (ref "X-NORTH") (pin "26") (pinfunction "26_26") (pintype "bidirectional"))
      (node (ref "X-WEST") (pin "61") (pinfunction "61_61") (pintype "bidirectional"))
    )
    (net (code "117") (name "OUT35_P") (class "Default")
      (node (ref "X-NORTH") (pin "28") (pinfunction "28_28") (pintype "bidirectional"))
      (node (ref "X-WEST") (pin "59") (pinfunction "59_59") (pintype "bidirectional"))
    )
    (net (code "118") (name "OUT36_N") (class "Default")
      (node (ref "X-NORTH") (pin "33") (pinfunction "33_33") (pintype "bidirectional"))
    )
    (net (code "119") (name "OUT36_P") (class "Default")
      (node (ref "X-NORTH") (pin "35") (pinfunction "35_35") (pintype "bidirectional"))
    )
    (net (code "120") (name "OUT37_N") (class "Default")
      (node (ref "X-NORTH") (pin "32") (pinfunction "32_32") (pintype "bidirectional"))
      (node (ref "X-WEST") (pin "47") (pinfunction "47_47") (pintype "bidirectional"))
    )
    (net (code "121") (name "OUT37_P") (class "Default")
      (node (ref "X-NORTH") (pin "34") (pinfunction "34_34") (pintype "bidirectional"))
      (node (ref "X-WEST") (pin "45") (pinfunction "45_45") (pintype "bidirectional"))
    )
    (net (code "122") (name "OUT38_N") (class "Default")
      (node (ref "X-NORTH") (pin "38") (pinfunction "38_38") (pintype "bidirectional"))
    )
    (net (code "123") (name "OUT38_P") (class "Default")
      (node (ref "X-NORTH") (pin "40") (pinfunction "40_40") (pintype "bidirectional"))
    )
    (net (code "124") (name "OUT39_N") (class "Default")
      (node (ref "X-NORTH") (pin "39") (pinfunction "39_39") (pintype "bidirectional"))
      (node (ref "X-WEST") (pin "80") (pinfunction "80_80") (pintype "bidirectional"))
    )
    (net (code "125") (name "OUT39_P") (class "Default")
      (node (ref "X-NORTH") (pin "41") (pinfunction "41_41") (pintype "bidirectional"))
      (node (ref "X-WEST") (pin "78") (pinfunction "78_78") (pintype "bidirectional"))
    )
    (net (code "126") (name "OUT40_N") (class "Default")
      (node (ref "X-NORTH") (pin "44") (pinfunction "44_44") (pintype "bidirectional"))
    )
    (net (code "127") (name "OUT40_P") (class "Default")
      (node (ref "X-NORTH") (pin "46") (pinfunction "46_46") (pintype "bidirectional"))
    )
    (net (code "128") (name "OUT41_N") (class "Default")
      (node (ref "X-NORTH") (pin "45") (pinfunction "45_45") (pintype "bidirectional"))
      (node (ref "X-WEST") (pin "74") (pinfunction "74_74") (pintype "bidirectional"))
    )
    (net (code "129") (name "OUT41_P") (class "Default")
      (node (ref "X-NORTH") (pin "47") (pinfunction "47_47") (pintype "bidirectional"))
      (node (ref "X-WEST") (pin "72") (pinfunction "72_72") (pintype "bidirectional"))
    )
    (net (code "130") (name "OUT42_N") (class "Default")
      (node (ref "X-NORTH") (pin "50") (pinfunction "50_50") (pintype "bidirectional"))
    )
    (net (code "131") (name "OUT42_P") (class "Default")
      (node (ref "X-NORTH") (pin "52") (pinfunction "52_52") (pintype "bidirectional"))
    )
    (net (code "132") (name "OUT43_N") (class "Default")
      (node (ref "X-NORTH") (pin "51") (pinfunction "51_51") (pintype "bidirectional"))
      (node (ref "X-WEST") (pin "68") (pinfunction "68_68") (pintype "bidirectional"))
    )
    (net (code "133") (name "OUT43_P") (class "Default")
      (node (ref "X-NORTH") (pin "53") (pinfunction "53_53") (pintype "bidirectional"))
      (node (ref "X-WEST") (pin "66") (pinfunction "66_66") (pintype "bidirectional"))
    )
    (net (code "134") (name "OUT44_N") (class "Default")
      (node (ref "X-NORTH") (pin "56") (pinfunction "56_56") (pintype "bidirectional"))
    )
    (net (code "135") (name "OUT44_P") (class "Default")
      (node (ref "X-NORTH") (pin "58") (pinfunction "58_58") (pintype "bidirectional"))
    )
    (net (code "136") (name "OUT45_N") (class "Default")
      (node (ref "X-NORTH") (pin "57") (pinfunction "57_57") (pintype "bidirectional"))
      (node (ref "X-WEST") (pin "62") (pinfunction "62_62") (pintype "bidirectional"))
    )
    (net (code "137") (name "OUT45_P") (class "Default")
      (node (ref "X-NORTH") (pin "59") (pinfunction "59_59") (pintype "bidirectional"))
      (node (ref "X-WEST") (pin "60") (pinfunction "60_60") (pintype "bidirectional"))
    )
    (net (code "138") (name "OUT46_N") (class "Default")
      (node (ref "X-NORTH") (pin "62") (pinfunction "62_62") (pintype "bidirectional"))
    )
    (net (code "139") (name "OUT46_P") (class "Default")
      (node (ref "X-NORTH") (pin "64") (pinfunction "64_64") (pintype "bidirectional"))
    )
    (net (code "140") (name "OUT47_N") (class "Default")
      (node (ref "X-NORTH") (pin "63") (pinfunction "63_63") (pintype "bidirectional"))
      (node (ref "X-WEST") (pin "56") (pinfunction "56_56") (pintype "bidirectional"))
    )
    (net (code "141") (name "OUT47_P") (class "Default")
      (node (ref "X-NORTH") (pin "65") (pinfunction "65_65") (pintype "bidirectional"))
      (node (ref "X-WEST") (pin "54") (pinfunction "54_54") (pintype "bidirectional"))
    )
    (net (code "142") (name "OUT48_N") (class "Default")
      (node (ref "X-NORTH") (pin "68") (pinfunction "68_68") (pintype "bidirectional"))
    )
    (net (code "143") (name "OUT48_P") (class "Default")
      (node (ref "X-NORTH") (pin "70") (pinfunction "70_70") (pintype "bidirectional"))
    )
    (net (code "144") (name "OUT49_N") (class "Default")
      (node (ref "X-EAST") (pin "48") (pinfunction "48_48") (pintype "bidirectional"))
      (node (ref "X-NORTH") (pin "74") (pinfunction "74_74") (pintype "bidirectional"))
    )
    (net (code "145") (name "OUT49_P") (class "Default")
      (node (ref "X-EAST") (pin "46") (pinfunction "46_46") (pintype "bidirectional"))
      (node (ref "X-NORTH") (pin "76") (pinfunction "76_76") (pintype "bidirectional"))
    )
    (net (code "146") (name "OUT50_N") (class "Default")
      (node (ref "X-NORTH") (pin "69") (pinfunction "69_69") (pintype "bidirectional"))
    )
    (net (code "147") (name "OUT50_P") (class "Default")
      (node (ref "X-NORTH") (pin "71") (pinfunction "71_71") (pintype "bidirectional"))
    )
    (net (code "148") (name "OUT51_N") (class "Default")
      (node (ref "X-EAST") (pin "42") (pinfunction "42_42") (pintype "bidirectional"))
      (node (ref "X-NORTH") (pin "80") (pinfunction "80_80") (pintype "bidirectional"))
    )
    (net (code "149") (name "OUT51_P") (class "Default")
      (node (ref "X-EAST") (pin "40") (pinfunction "40_40") (pintype "bidirectional"))
      (node (ref "X-NORTH") (pin "82") (pinfunction "82_82") (pintype "bidirectional"))
    )
    (net (code "150") (name "OUT52_N") (class "Default")
      (node (ref "X-NORTH") (pin "75") (pinfunction "75_75") (pintype "bidirectional"))
    )
    (net (code "151") (name "OUT52_P") (class "Default")
      (node (ref "X-NORTH") (pin "77") (pinfunction "77_77") (pintype "bidirectional"))
    )
    (net (code "152") (name "OUT53_N") (class "Default")
      (node (ref "X-EAST") (pin "47") (pinfunction "47_47") (pintype "bidirectional"))
      (node (ref "X-NORTH") (pin "86") (pinfunction "86_86") (pintype "bidirectional"))
    )
    (net (code "153") (name "OUT53_P") (class "Default")
      (node (ref "X-EAST") (pin "45") (pinfunction "45_45") (pintype "bidirectional"))
      (node (ref "X-NORTH") (pin "88") (pinfunction "88_88") (pintype "bidirectional"))
    )
    (net (code "154") (name "OUT54_N") (class "Default")
      (node (ref "X-NORTH") (pin "81") (pinfunction "81_81") (pintype "bidirectional"))
    )
    (net (code "155") (name "OUT54_P") (class "Default")
      (node (ref "X-NORTH") (pin "83") (pinfunction "83_83") (pintype "bidirectional"))
    )
    (net (code "156") (name "OUT55_N") (class "Default")
      (node (ref "X-EAST") (pin "41") (pinfunction "41_41") (pintype "bidirectional"))
      (node (ref "X-NORTH") (pin "92") (pinfunction "92_92") (pintype "bidirectional"))
    )
    (net (code "157") (name "OUT55_P") (class "Default")
      (node (ref "X-EAST") (pin "39") (pinfunction "39_39") (pintype "bidirectional"))
      (node (ref "X-NORTH") (pin "94") (pinfunction "94_94") (pintype "bidirectional"))
    )
    (net (code "158") (name "OUT56_N") (class "Default")
      (node (ref "X-NORTH") (pin "87") (pinfunction "87_87") (pintype "bidirectional"))
    )
    (net (code "159") (name "OUT56_P") (class "Default")
      (node (ref "X-NORTH") (pin "89") (pinfunction "89_89") (pintype "bidirectional"))
    )
    (net (code "160") (name "OUT57_N") (class "Default")
      (node (ref "X-EAST") (pin "35") (pinfunction "35_35") (pintype "bidirectional"))
      (node (ref "X-NORTH") (pin "98") (pinfunction "98_98") (pintype "bidirectional"))
    )
    (net (code "161") (name "OUT57_P") (class "Default")
      (node (ref "X-EAST") (pin "33") (pinfunction "33_33") (pintype "bidirectional"))
      (node (ref "X-NORTH") (pin "100") (pinfunction "100_100") (pintype "bidirectional"))
    )
    (net (code "162") (name "OUT58_N") (class "Default")
      (node (ref "X-NORTH") (pin "93") (pinfunction "93_93") (pintype "bidirectional"))
    )
    (net (code "163") (name "OUT58_P") (class "Default")
      (node (ref "X-NORTH") (pin "95") (pinfunction "95_95") (pintype "bidirectional"))
    )
    (net (code "164") (name "OUT59_N") (class "Default")
      (node (ref "X-EAST") (pin "27") (pinfunction "27_27") (pintype "bidirectional"))
      (node (ref "X-NORTH") (pin "104") (pinfunction "104_104") (pintype "bidirectional"))
    )
    (net (code "165") (name "OUT59_P") (class "Default")
      (node (ref "X-EAST") (pin "25") (pinfunction "25_25") (pintype "bidirectional"))
      (node (ref "X-NORTH") (pin "106") (pinfunction "106_106") (pintype "bidirectional"))
    )
    (net (code "166") (name "OUT60_N") (class "Default")
      (node (ref "X-NORTH") (pin "110") (pinfunction "110_110") (pintype "bidirectional"))
    )
    (net (code "167") (name "OUT60_P") (class "Default")
      (node (ref "X-NORTH") (pin "112") (pinfunction "112_112") (pintype "bidirectional"))
    )
    (net (code "168") (name "OUT61_N") (class "Default")
      (node (ref "X-EAST") (pin "36") (pinfunction "36_36") (pintype "bidirectional"))
      (node (ref "X-NORTH") (pin "99") (pinfunction "99_99") (pintype "bidirectional"))
    )
    (net (code "169") (name "OUT61_P") (class "Default")
      (node (ref "X-EAST") (pin "34") (pinfunction "34_34") (pintype "bidirectional"))
      (node (ref "X-NORTH") (pin "101") (pinfunction "101_101") (pintype "bidirectional"))
    )
    (net (code "170") (name "OUT62_N") (class "Default")
      (node (ref "X-NORTH") (pin "116") (pinfunction "116_116") (pintype "bidirectional"))
    )
    (net (code "171") (name "OUT62_P") (class "Default")
      (node (ref "X-NORTH") (pin "118") (pinfunction "118_118") (pintype "bidirectional"))
    )
    (net (code "172") (name "OUT63_N") (class "Default")
      (node (ref "X-EAST") (pin "30") (pinfunction "30_30") (pintype "bidirectional"))
      (node (ref "X-NORTH") (pin "105") (pinfunction "105_105") (pintype "bidirectional"))
    )
    (net (code "173") (name "OUT63_P") (class "Default")
      (node (ref "X-EAST") (pin "28") (pinfunction "28_28") (pintype "bidirectional"))
      (node (ref "X-NORTH") (pin "107") (pinfunction "107_107") (pintype "bidirectional"))
    )
    (net (code "174") (name "OUT64_N") (class "Default")
      (node (ref "X-NORTH") (pin "111") (pinfunction "111_111") (pintype "bidirectional"))
    )
    (net (code "175") (name "OUT64_P") (class "Default")
      (node (ref "X-NORTH") (pin "113") (pinfunction "113_113") (pintype "bidirectional"))
    )
    (net (code "176") (name "OUTCLK_N") (class "Default")
      (node (ref "X-NORTH") (pin "15") (pinfunction "15_15") (pintype "bidirectional"))
      (node (ref "X-WEST") (pin "53") (pinfunction "53_53") (pintype "bidirectional"))
    )
    (net (code "177") (name "OUTCLK_P") (class "Default")
      (node (ref "X-NORTH") (pin "17") (pinfunction "17_17") (pintype "bidirectional"))
      (node (ref "X-WEST") (pin "55") (pinfunction "55_55") (pintype "bidirectional"))
    )
    (net (code "178") (name "OUTCTR_N") (class "Default")
      (node (ref "X-SOUTH") (pin "125") (pinfunction "125_125") (pintype "bidirectional"))
      (node (ref "X-WEST") (pin "22") (pinfunction "22_22") (pintype "bidirectional"))
    )
    (net (code "179") (name "OUTCTR_P") (class "Default")
      (node (ref "X-SOUTH") (pin "123") (pinfunction "123_123") (pintype "bidirectional"))
      (node (ref "X-WEST") (pin "24") (pinfunction "24_24") (pintype "bidirectional"))
    )
    (net (code "180") (name "RES1") (class "Default")
      (node (ref "X-WEST") (pin "79") (pinfunction "79_79") (pintype "bidirectional"))
    )
    (net (code "181") (name "RES2") (class "Default")
      (node (ref "X-WEST") (pin "81") (pinfunction "81_81") (pintype "bidirectional"))
    )
    (net (code "182") (name "RES3") (class "Default")
      (node (ref "X-WEST") (pin "83") (pinfunction "83_83") (pintype "bidirectional"))
    )
    (net (code "183") (name "RES4") (class "Default")
      (node (ref "X-EAST") (pin "79") (pinfunction "79_79") (pintype "bidirectional"))
    )
    (net (code "184") (name "RES5") (class "Default")
      (node (ref "X-EAST") (pin "81") (pinfunction "81_81") (pintype "bidirectional"))
    )
    (net (code "185") (name "RES6") (class "Default")
      (node (ref "X-EAST") (pin "83") (pinfunction "83_83") (pintype "bidirectional"))
    )
    (net (code "186") (name "S00_N") (class "Default")
      (node (ref "X-SOUTH") (pin "16") (pinfunction "16_16") (pintype "bidirectional"))
    )
    (net (code "187") (name "S00_P") (class "Default")
      (node (ref "X-SOUTH") (pin "14") (pinfunction "14_14") (pintype "bidirectional"))
    )
    (net (code "188") (name "S01_N") (class "Default")
      (node (ref "X-SOUTH") (pin "17") (pinfunction "17_17") (pintype "bidirectional"))
    )
    (net (code "189") (name "S01_P") (class "Default")
      (node (ref "X-SOUTH") (pin "15") (pinfunction "15_15") (pintype "bidirectional"))
    )
    (net (code "190") (name "S02_N") (class "Default")
      (node (ref "X-SOUTH") (pin "22") (pinfunction "22_22") (pintype "bidirectional"))
    )
    (net (code "191") (name "S02_P") (class "Default")
      (node (ref "X-SOUTH") (pin "20") (pinfunction "20_20") (pintype "bidirectional"))
    )
    (net (code "192") (name "S03_N") (class "Default")
      (node (ref "X-SOUTH") (pin "23") (pinfunction "23_23") (pintype "bidirectional"))
    )
    (net (code "193") (name "S03_P") (class "Default")
      (node (ref "X-SOUTH") (pin "21") (pinfunction "21_21") (pintype "bidirectional"))
    )
    (net (code "194") (name "S05_N") (class "Default")
      (node (ref "X-SOUTH") (pin "29") (pinfunction "29_29") (pintype "bidirectional"))
    )
    (net (code "195") (name "S05_P") (class "Default")
      (node (ref "X-SOUTH") (pin "27") (pinfunction "27_27") (pintype "bidirectional"))
    )
    (net (code "196") (name "S38_N") (class "Default")
      (node (ref "X-SOUTH") (pin "130") (pinfunction "130_130") (pintype "bidirectional"))
    )
    (net (code "197") (name "S38_P") (class "Default")
      (node (ref "X-SOUTH") (pin "128") (pinfunction "128_128") (pintype "bidirectional"))
    )
    (net (code "198") (name "S39_N") (class "Default")
      (node (ref "X-SOUTH") (pin "131") (pinfunction "131_131") (pintype "bidirectional"))
    )
    (net (code "199") (name "S39_P") (class "Default")
      (node (ref "X-SOUTH") (pin "129") (pinfunction "129_129") (pintype "bidirectional"))
    )
    (net (code "200") (name "SYS_RES_N") (class "Default")
      (node (ref "X-EAST") (pin "22") (pinfunction "22_22") (pintype "bidirectional"))
      (node (ref "X-NORTH") (pin "125") (pinfunction "125_125") (pintype "bidirectional"))
    )
    (net (code "201") (name "S_CHK_EN") (class "Default")
      (node (ref "X-EAST") (pin "94") (pinfunction "94_94") (pintype "bidirectional"))
      (node (ref "X-SOUTH") (pin "8") (pinfunction "8_8") (pintype "bidirectional"))
    )
    (net (code "202") (name "S_CHK_V") (class "Default")
      (node (ref "X-EAST") (pin "92") (pinfunction "92_92") (pintype "bidirectional"))
      (node (ref "X-SOUTH") (pin "10") (pinfunction "10_10") (pintype "bidirectional"))
    )
    (net (code "203") (name "S_I2C_EN") (class "Default")
      (node (ref "X-SOUTH") (pin "137") (pinfunction "137_137") (pintype "bidirectional"))
      (node (ref "X-WEST") (pin "7") (pinfunction "7_7") (pintype "bidirectional"))
    )
    (net (code "204") (name "S_I2C_V") (class "Default")
      (node (ref "X-SOUTH") (pin "135") (pinfunction "135_135") (pintype "bidirectional"))
      (node (ref "X-WEST") (pin "9") (pinfunction "9_9") (pintype "bidirectional"))
    )
    (net (code "205") (name "S_SCK") (class "Default")
      (node (ref "X-SOUTH") (pin "144") (pinfunction "144_144") (pintype "bidirectional"))
      (node (ref "X-WEST") (pin "2") (pinfunction "2_2") (pintype "bidirectional"))
    )
    (net (code "206") (name "S_SCL") (class "Default")
      (node (ref "X-SOUTH") (pin "143") (pinfunction "143_143") (pintype "bidirectional"))
      (node (ref "X-WEST") (pin "1") (pinfunction "1_1") (pintype "bidirectional"))
    )
    (net (code "207") (name "S_SDA") (class "Default")
      (node (ref "X-SOUTH") (pin "141") (pinfunction "141_141") (pintype "bidirectional"))
      (node (ref "X-WEST") (pin "3") (pinfunction "3_3") (pintype "bidirectional"))
    )
    (net (code "208") (name "S_SDI") (class "Default")
      (node (ref "X-SOUTH") (pin "140") (pinfunction "140_140") (pintype "bidirectional"))
      (node (ref "X-WEST") (pin "6") (pinfunction "6_6") (pintype "bidirectional"))
    )
    (net (code "209") (name "S_SDO") (class "Default")
      (node (ref "X-SOUTH") (pin "142") (pinfunction "142_142") (pintype "bidirectional"))
      (node (ref "X-WEST") (pin "4") (pinfunction "4_4") (pintype "bidirectional"))
    )
    (net (code "210") (name "S_SPI_EN") (class "Default")
      (node (ref "X-SOUTH") (pin "136") (pinfunction "136_136") (pintype "bidirectional"))
      (node (ref "X-WEST") (pin "8") (pinfunction "8_8") (pintype "bidirectional"))
    )
    (net (code "211") (name "S_SPI_V") (class "Default")
      (node (ref "X-SOUTH") (pin "134") (pinfunction "134_134") (pintype "bidirectional"))
      (node (ref "X-WEST") (pin "10") (pinfunction "10_10") (pintype "bidirectional"))
    )
    (net (code "212") (name "S_VE") (class "Default")
      (node (ref "C7") (pin "1") (pinfunction "1_1") (pintype "passive"))
      (node (ref "SE") (pin "1") (pinfunction "1_1") (pintype "passive"))
      (node (ref "X-SOUTH") (pin "13") (pinfunction "13_13") (pintype "bidirectional"))
      (node (ref "X-SOUTH") (pin "19") (pinfunction "19_19") (pintype "bidirectional"))
      (node (ref "X-SOUTH") (pin "31") (pinfunction "31_31") (pintype "bidirectional"))
      (node (ref "X-SOUTH") (pin "37") (pinfunction "37_37") (pintype "bidirectional"))
    )
    (net (code "213") (name "S_VE_CV") (class "Default")
      (node (ref "X-EAST") (pin "100") (pinfunction "100_100") (pintype "bidirectional"))
      (node (ref "X-SOUTH") (pin "2") (pinfunction "2_2") (pintype "bidirectional"))
    )
    (net (code "214") (name "S_VE_OV") (class "Default")
      (node (ref "X-EAST") (pin "99") (pinfunction "99_99") (pintype "bidirectional"))
      (node (ref "X-SOUTH") (pin "1") (pinfunction "1_1") (pintype "bidirectional"))
    )
    (net (code "215") (name "S_VE_RS") (class "Default")
      (node (ref "X-EAST") (pin "84") (pinfunction "84_84") (pintype "bidirectional"))
      (node (ref "X-SOUTH") (pin "25") (pinfunction "25_25") (pintype "bidirectional"))
    )
    (net (code "216") (name "S_VE_UV") (class "Default")
      (node (ref "X-EAST") (pin "89") (pinfunction "89_89") (pintype "bidirectional"))
      (node (ref "X-SOUTH") (pin "7") (pinfunction "7_7") (pintype "bidirectional"))
    )
    (net (code "217") (name "S_VS") (class "Default")
      (node (ref "C6") (pin "1") (pinfunction "1_1") (pintype "passive"))
      (node (ref "SW") (pin "1") (pinfunction "1_1") (pintype "passive"))
      (node (ref "X-SOUTH") (pin "49") (pinfunction "49_49") (pintype "bidirectional"))
      (node (ref "X-SOUTH") (pin "55") (pinfunction "55_55") (pintype "bidirectional"))
      (node (ref "X-SOUTH") (pin "61") (pinfunction "61_61") (pintype "bidirectional"))
      (node (ref "X-SOUTH") (pin "67") (pinfunction "67_67") (pintype "bidirectional"))
      (node (ref "X-SOUTH") (pin "79") (pinfunction "79_79") (pintype "bidirectional"))
      (node (ref "X-SOUTH") (pin "85") (pinfunction "85_85") (pintype "bidirectional"))
      (node (ref "X-SOUTH") (pin "91") (pinfunction "91_91") (pintype "bidirectional"))
      (node (ref "X-SOUTH") (pin "97") (pinfunction "97_97") (pintype "bidirectional"))
    )
    (net (code "218") (name "S_VS_CV") (class "Default")
      (node (ref "X-EAST") (pin "98") (pinfunction "98_98") (pintype "bidirectional"))
      (node (ref "X-SOUTH") (pin "4") (pinfunction "4_4") (pintype "bidirectional"))
    )
    (net (code "219") (name "S_VS_OV") (class "Default")
      (node (ref "X-EAST") (pin "97") (pinfunction "97_97") (pintype "bidirectional"))
      (node (ref "X-SOUTH") (pin "3") (pinfunction "3_3") (pintype "bidirectional"))
    )
    (net (code "220") (name "S_VS_RS") (class "Default")
      (node (ref "X-EAST") (pin "86") (pinfunction "86_86") (pintype "bidirectional"))
      (node (ref "X-SOUTH") (pin "73") (pinfunction "73_73") (pintype "bidirectional"))
    )
    (net (code "221") (name "S_VS_UV") (class "Default")
      (node (ref "X-EAST") (pin "87") (pinfunction "87_87") (pintype "bidirectional"))
      (node (ref "X-SOUTH") (pin "9") (pinfunction "9_9") (pintype "bidirectional"))
    )
    (net (code "222") (name "S_VW") (class "Default")
      (node (ref "C2") (pin "1") (pinfunction "1_1") (pintype "passive"))
      (node (ref "SW") (pin "2") (pinfunction "2_2") (pintype "passive"))
      (node (ref "X-SOUTH") (pin "109") (pinfunction "109_109") (pintype "bidirectional"))
      (node (ref "X-SOUTH") (pin "115") (pinfunction "115_115") (pintype "bidirectional"))
      (node (ref "X-SOUTH") (pin "127") (pinfunction "127_127") (pintype "bidirectional"))
      (node (ref "X-SOUTH") (pin "133") (pinfunction "133_133") (pintype "bidirectional"))
    )
    (net (code "223") (name "S_VW_CV") (class "Default")
      (node (ref "X-EAST") (pin "96") (pinfunction "96_96") (pintype "bidirectional"))
      (node (ref "X-SOUTH") (pin "6") (pinfunction "6_6") (pintype "bidirectional"))
    )
    (net (code "224") (name "S_VW_OV") (class "Default")
      (node (ref "X-EAST") (pin "95") (pinfunction "95_95") (pintype "bidirectional"))
      (node (ref "X-SOUTH") (pin "5") (pinfunction "5_5") (pintype "bidirectional"))
    )
    (net (code "225") (name "S_VW_RS") (class "Default")
      (node (ref "X-EAST") (pin "88") (pinfunction "88_88") (pintype "bidirectional"))
      (node (ref "X-SOUTH") (pin "121") (pinfunction "121_121") (pintype "bidirectional"))
    )
    (net (code "226") (name "S_VW_UV") (class "Default")
      (node (ref "X-EAST") (pin "85") (pinfunction "85_85") (pintype "bidirectional"))
      (node (ref "X-SOUTH") (pin "11") (pinfunction "11_11") (pintype "bidirectional"))
    )
    (net (code "227") (name "TCK") (class "Default")
      (node (ref "X-WEST") (pin "12") (pinfunction "12_12") (pintype "bidirectional"))
    )
    (net (code "228") (name "TDI") (class "Default")
      (node (ref "X-WEST") (pin "16") (pinfunction "16_16") (pintype "bidirectional"))
    )
    (net (code "229") (name "TDIG1") (class "Default")
      (node (ref "X-EAST") (pin "18") (pinfunction "18_18") (pintype "bidirectional"))
      (node (ref "X-NORTH") (pin "123") (pinfunction "123_123") (pintype "bidirectional"))
    )
    (net (code "230") (name "TDIG2") (class "Default")
      (node (ref "X-NORTH") (pin "130") (pinfunction "130_130") (pintype "bidirectional"))
    )
    (net (code "231") (name "TDO") (class "Default")
      (node (ref "X-WEST") (pin "18") (pinfunction "18_18") (pintype "bidirectional"))
    )
    (net (code "232") (name "TMS") (class "Default")
      (node (ref "X-WEST") (pin "14") (pinfunction "14_14") (pintype "bidirectional"))
    )
    (net (code "233") (name "TP9") (class "Default")
      (node (ref "X-NORTH") (pin "119") (pinfunction "119_119") (pintype "bidirectional"))
    )
    (net (code "234") (name "T_EXP1") (class "Default")
      (node (ref "X-EAST") (pin "12") (pinfunction "12_12") (pintype "bidirectional"))
      (node (ref "X-NORTH") (pin "131") (pinfunction "131_131") (pintype "bidirectional"))
    )
    (net (code "235") (name "T_EXP2") (class "Default")
      (node (ref "X-EAST") (pin "16") (pinfunction "16_16") (pintype "bidirectional"))
      (node (ref "X-NORTH") (pin "117") (pinfunction "117_117") (pintype "bidirectional"))
    )
    (net (code "236") (name "W_EN") (class "Default")
      (node (ref "X-WEST") (pin "19") (pinfunction "19_19") (pintype "bidirectional"))
    )
    (net (code "237") (name "W_I2C_EN") (class "Default")
      (node (ref "X-WEST") (pin "13") (pinfunction "13_13") (pintype "bidirectional"))
    )
    (net (code "238") (name "W_I2C_V") (class "Default")
      (node (ref "X-WEST") (pin "11") (pinfunction "11_11") (pintype "bidirectional"))
    )
    (net (code "239") (name "W_SCL") (class "Default")
      (node (ref "X-WEST") (pin "15") (pinfunction "15_15") (pintype "bidirectional"))
    )
    (net (code "240") (name "W_SDA") (class "Default")
      (node (ref "X-WEST") (pin "17") (pinfunction "17_17") (pintype "bidirectional"))
    )
    (net (code "241") (name "W_VW") (class "Default")
      (node (ref "C8") (pin "1") (pinfunction "1_1") (pintype "passive"))
      (node (ref "NW") (pin "2") (pinfunction "2_2") (pintype "passive"))
    )
    (net (code "242") (name "W_VW_CV") (class "Default")
      (node (ref "X-WEST") (pin "90") (pinfunction "90_90") (pintype "bidirectional"))
    )
    (net (code "243") (name "W_VW_OV") (class "Default")
      (node (ref "X-WEST") (pin "93") (pinfunction "93_93") (pintype "bidirectional"))
    )
    (net (code "244") (name "W_VW_UV") (class "Default")
      (node (ref "X-WEST") (pin "91") (pinfunction "91_91") (pintype "bidirectional"))
    )
    (net (code "245") (name "unconnected-(X-EAST-PadM1)") (class "Default")
      (node (ref "X-EAST") (pin "M1") (pinfunction "M1_M1") (pintype "bidirectional"))
    )
    (net (code "246") (name "unconnected-(X-EAST-PadM2)") (class "Default")
      (node (ref "X-EAST") (pin "M2") (pinfunction "M2_M2") (pintype "bidirectional"))
    )
    (net (code "247") (name "unconnected-(X-NORTH-PadM1)") (class "Default")
      (node (ref "X-NORTH") (pin "M1") (pinfunction "M1_M1") (pintype "bidirectional"))
    )
    (net (code "248") (name "unconnected-(X-NORTH-PadM2)") (class "Default")
      (node (ref "X-NORTH") (pin "M2") (pinfunction "M2_M2") (pintype "bidirectional"))
    )
    (net (code "249") (name "unconnected-(X-SOUTH-PadM1)") (class "Default")
      (node (ref "X-SOUTH") (pin "M1") (pinfunction "M1_M1") (pintype "bidirectional"))
    )
    (net (code "250") (name "unconnected-(X-SOUTH-PadM2)") (class "Default")
      (node (ref "X-SOUTH") (pin "M2") (pinfunction "M2_M2") (pintype "bidirectional"))
    )
    (net (code "251") (name "unconnected-(X-WEST-PadM1)") (class "Default")
      (node (ref "X-WEST") (pin "M1") (pinfunction "M1_M1") (pintype "bidirectional"))
    )
    (net (code "252") (name "unconnected-(X-WEST-PadM2)") (class "Default")
      (node (ref "X-WEST") (pin "M2") (pinfunction "M2_M2") (pintype "bidirectional"))
    )
  )
)
